# bontor_mbed_lowpan_rev_a.net
KiCad netlist of a schematic drawn in EAGLE
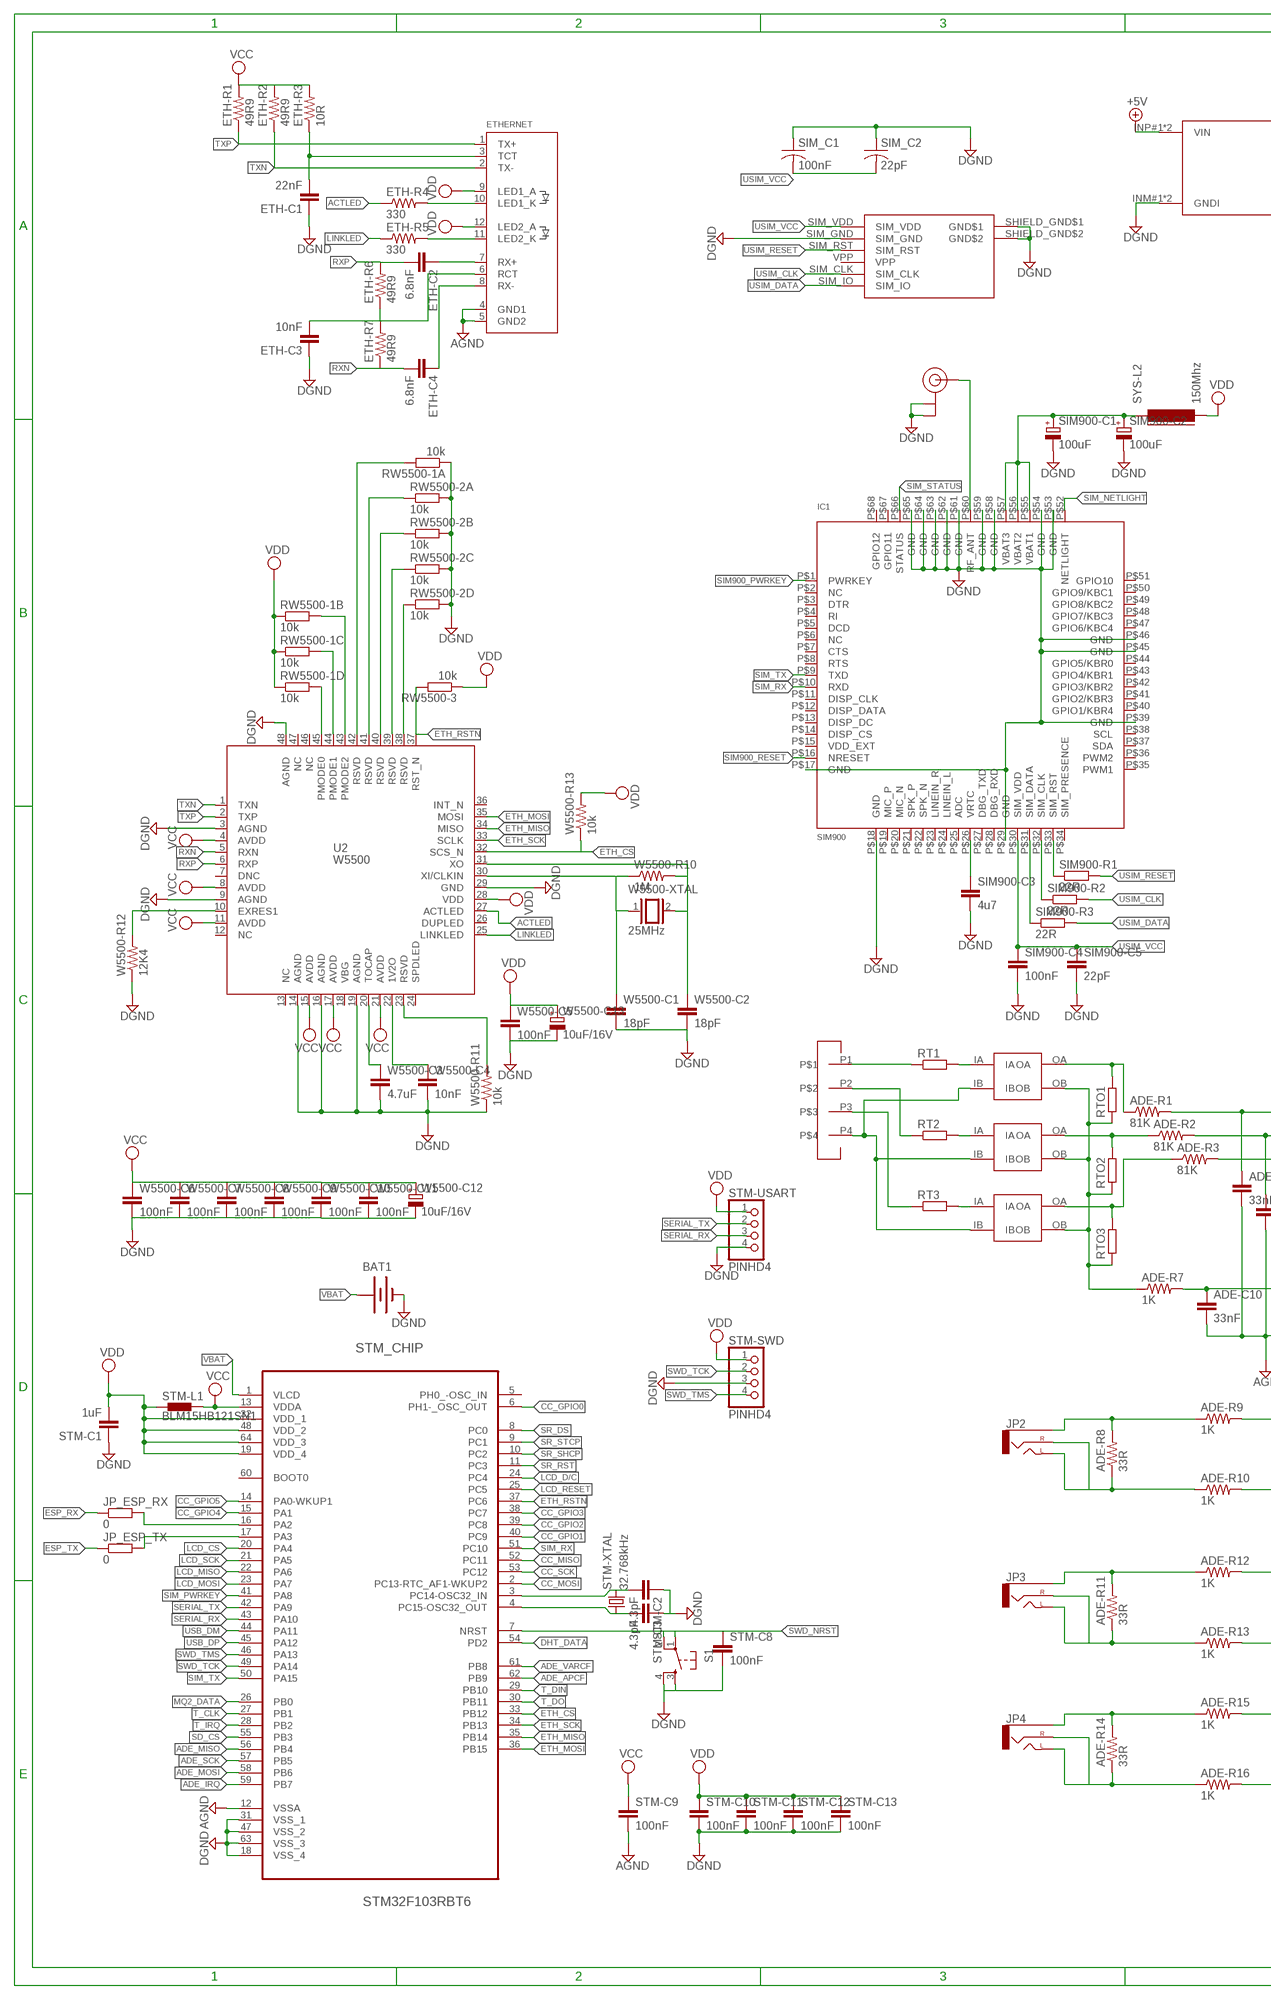
[diagram p0: schematic, sheet 1, part 1 of 2]
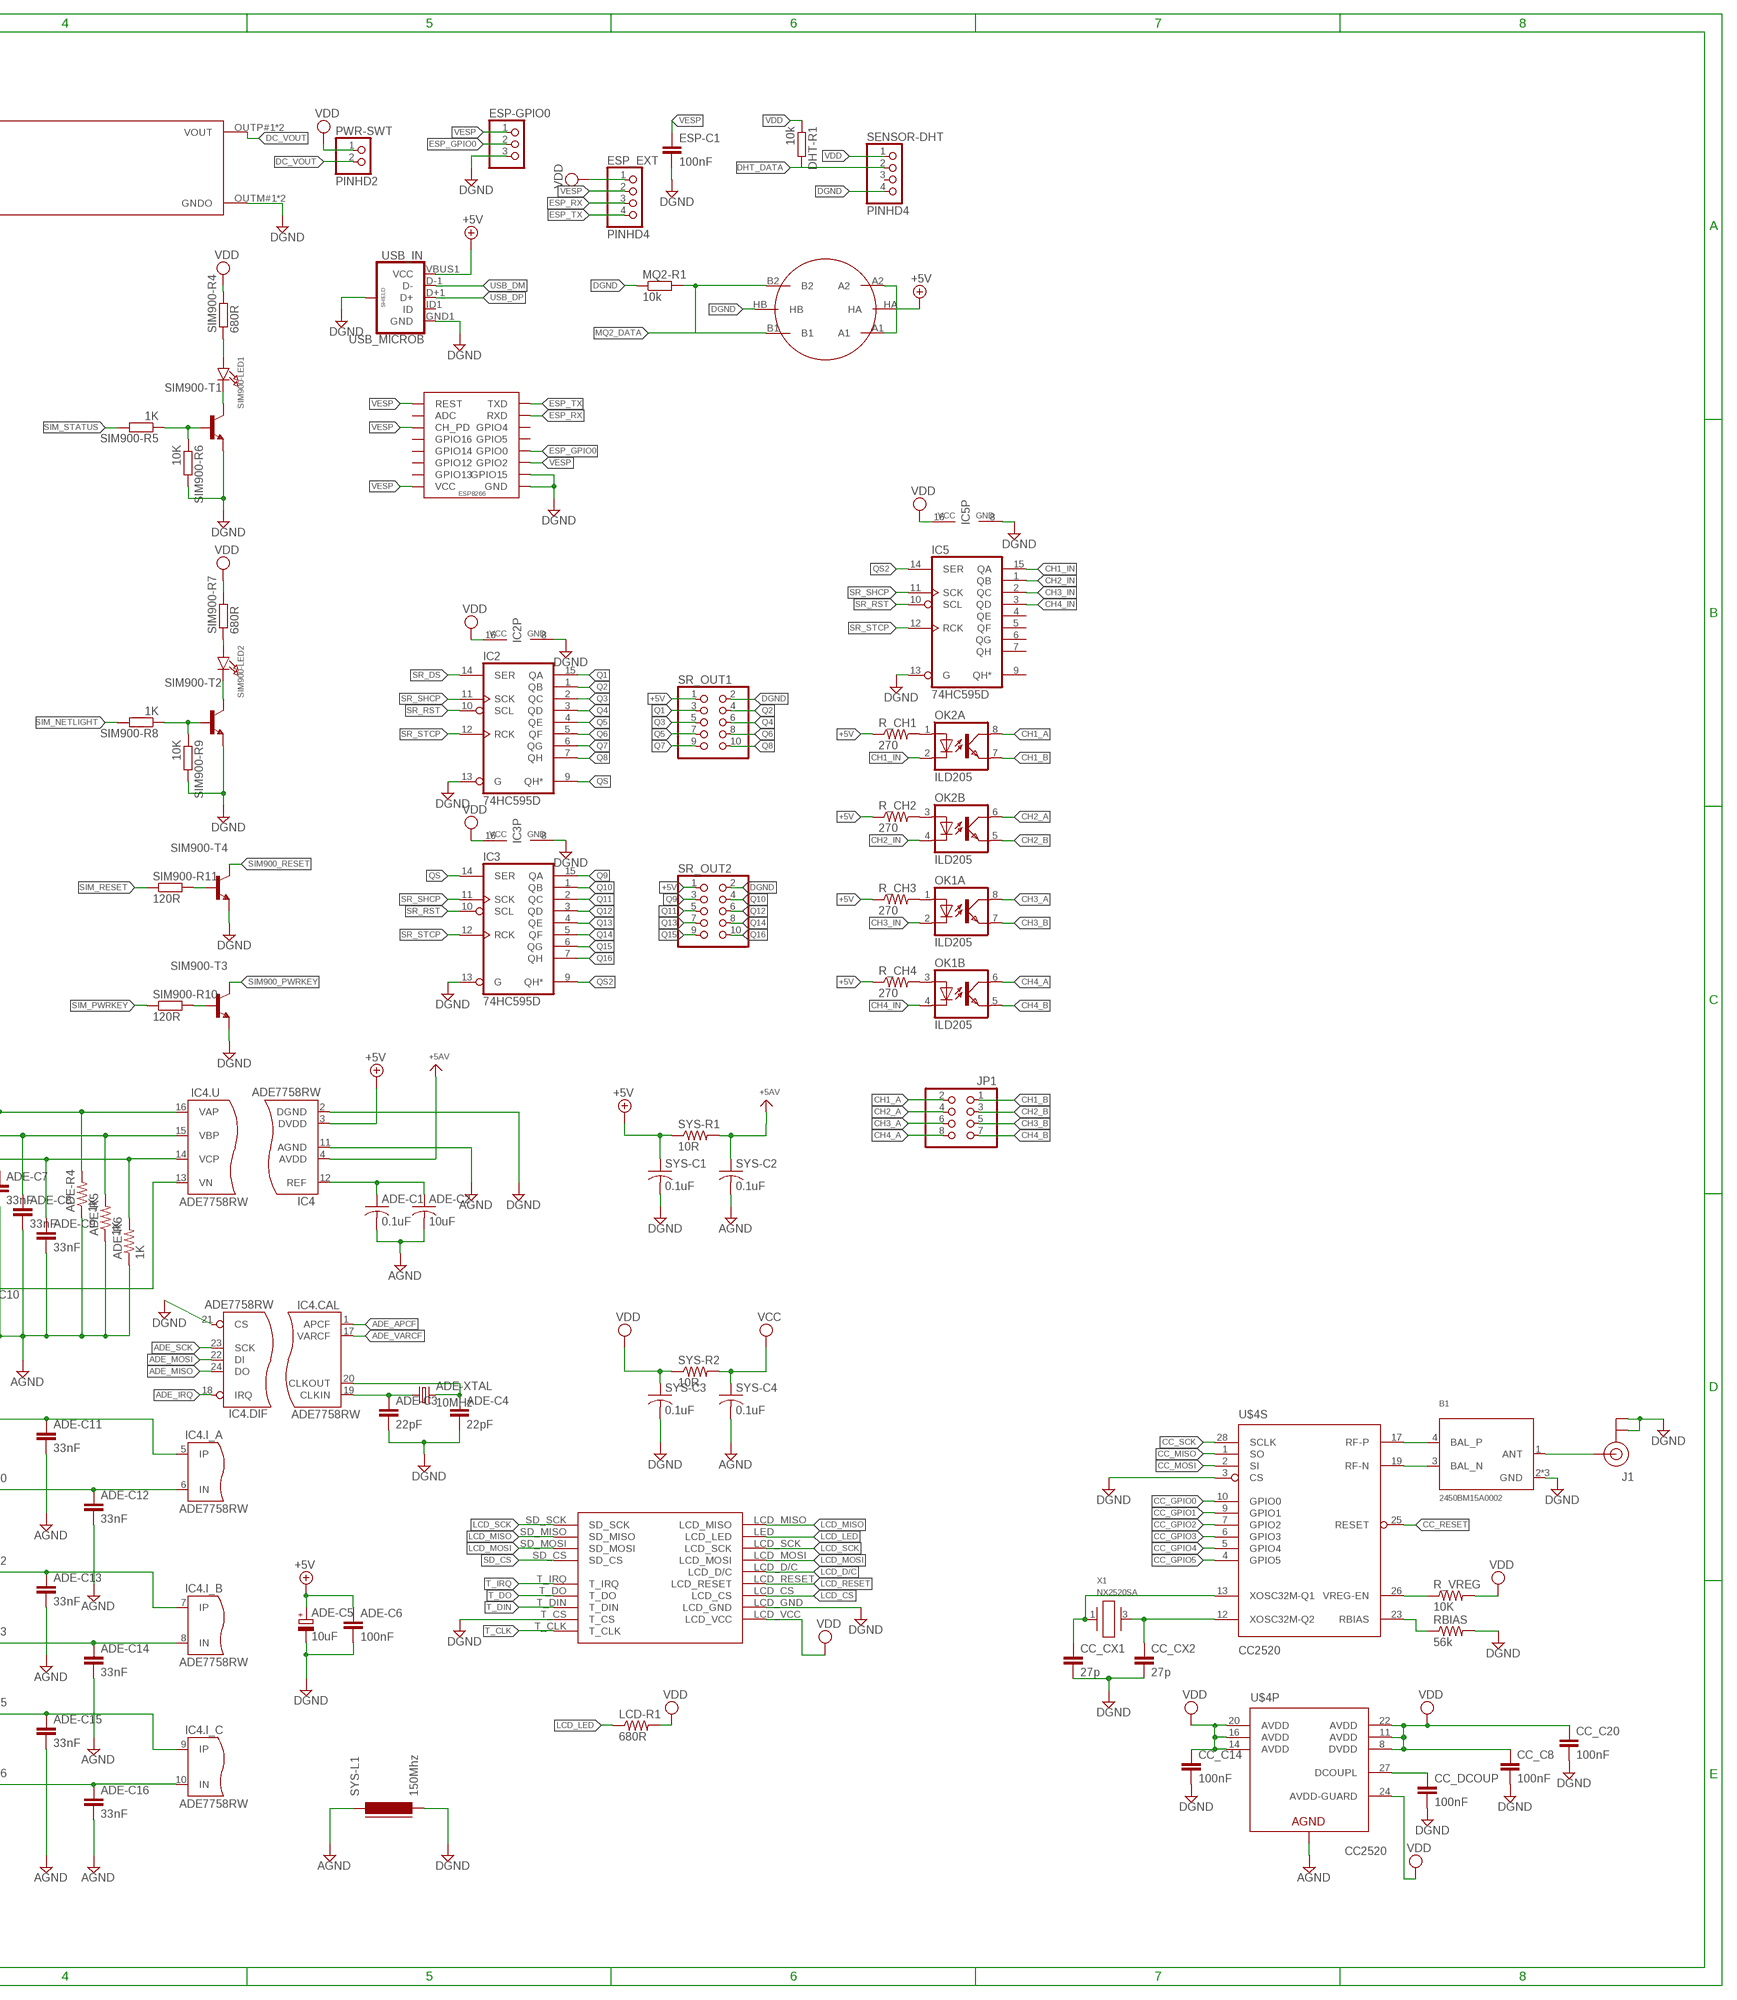
[diagram p1: schematic, sheet 1, part 2 of 2]

(export (version "E")
  (design (tool "Eeschema 10.0.6"))
  (components
    (comp (ref "ADE-C1")
      (value "0.1uF")
      (footprint "eagle-import:C0603@1")
      (libsource (lib "eagle-import") (part "C-USC0603"))
    )
    (comp (ref "ADE-C2")
      (value "10uF")
      (footprint "eagle-import:C0805K")
      (libsource (lib "eagle-import") (part "C-USC0805K"))
    )
    (comp (ref "ADE-C3")
      (value "22pF")
      (footprint "eagle-import:C0603")
      (libsource (lib "eagle-import") (part "C-EUC0603"))
    )
    (comp (ref "ADE-C4")
      (value "22pF")
      (footprint "eagle-import:C0603")
      (libsource (lib "eagle-import") (part "C-EUC0603"))
    )
    (comp (ref "ADE-C5")
      (value "10uF")
      (footprint "eagle-import:153CLV-0605")
      (libsource (lib "eagle-import") (part "CPOL-EU153CLV-0605"))
    )
    (comp (ref "ADE-C6")
      (value "100nF")
      (footprint "eagle-import:C0603")
      (libsource (lib "eagle-import") (part "C-EUC0603"))
    )
    (comp (ref "ADE-C7")
      (value "33nF")
      (footprint "eagle-import:0603-CAP")
      (libsource (lib "eagle-import") (part "CAP0603-CAP"))
    )
    (comp (ref "ADE-C8")
      (value "33nF")
      (footprint "eagle-import:0603-CAP")
      (libsource (lib "eagle-import") (part "CAP0603-CAP"))
    )
    (comp (ref "ADE-C9")
      (value "33nF")
      (footprint "eagle-import:0603-CAP")
      (libsource (lib "eagle-import") (part "CAP0603-CAP"))
    )
    (comp (ref "ADE-C10")
      (value "33nF")
      (footprint "eagle-import:0603-CAP")
      (libsource (lib "eagle-import") (part "CAP0603-CAP"))
    )
    (comp (ref "ADE-C11")
      (value "33nF")
      (footprint "eagle-import:0603-CAP")
      (libsource (lib "eagle-import") (part "CAP0603-CAP"))
    )
    (comp (ref "ADE-C12")
      (value "33nF")
      (footprint "eagle-import:0603-CAP")
      (libsource (lib "eagle-import") (part "CAP0603-CAP"))
    )
    (comp (ref "ADE-C13")
      (value "33nF")
      (footprint "eagle-import:0603-CAP")
      (libsource (lib "eagle-import") (part "CAP0603-CAP"))
    )
    (comp (ref "ADE-C14")
      (value "33nF")
      (footprint "eagle-import:0603-CAP")
      (libsource (lib "eagle-import") (part "CAP0603-CAP"))
    )
    (comp (ref "ADE-C15")
      (value "33nF")
      (footprint "eagle-import:0603-CAP")
      (libsource (lib "eagle-import") (part "CAP0603-CAP"))
    )
    (comp (ref "ADE-C16")
      (value "33nF")
      (footprint "eagle-import:0603-CAP")
      (libsource (lib "eagle-import") (part "CAP0603-CAP"))
    )
    (comp (ref "ADE-R1")
      (value "81K")
      (footprint "eagle-import:0603-RES")
      (libsource (lib "eagle-import") (part "RESISTOR0603-RES"))
    )
    (comp (ref "ADE-R2")
      (value "81K")
      (footprint "eagle-import:0603-RES")
      (libsource (lib "eagle-import") (part "RESISTOR0603-RES"))
    )
    (comp (ref "ADE-R3")
      (value "81K")
      (footprint "eagle-import:0603-RES")
      (libsource (lib "eagle-import") (part "RESISTOR0603-RES"))
    )
    (comp (ref "ADE-R4")
      (value "1K")
      (footprint "eagle-import:0603-RES")
      (libsource (lib "eagle-import") (part "RESISTOR0603-RES"))
    )
    (comp (ref "ADE-R5")
      (value "1K")
      (footprint "eagle-import:0603-RES")
      (libsource (lib "eagle-import") (part "RESISTOR0603-RES"))
    )
    (comp (ref "ADE-R6")
      (value "1K")
      (footprint "eagle-import:0603-RES")
      (libsource (lib "eagle-import") (part "RESISTOR0603-RES"))
    )
    (comp (ref "ADE-R7")
      (value "1K")
      (footprint "eagle-import:0603-RES")
      (libsource (lib "eagle-import") (part "RESISTOR0603-RES"))
    )
    (comp (ref "ADE-R8")
      (value "33R")
      (footprint "eagle-import:0603-RES")
      (libsource (lib "eagle-import") (part "RESISTOR0603-RES"))
    )
    (comp (ref "ADE-R9")
      (value "1K")
      (footprint "eagle-import:0603-RES")
      (libsource (lib "eagle-import") (part "RESISTOR0603-RES"))
    )
    (comp (ref "ADE-R10")
      (value "1K")
      (footprint "eagle-import:0603-RES")
      (libsource (lib "eagle-import") (part "RESISTOR0603-RES"))
    )
    (comp (ref "ADE-R11")
      (value "33R")
      (footprint "eagle-import:0603-RES")
      (libsource (lib "eagle-import") (part "RESISTOR0603-RES"))
    )
    (comp (ref "ADE-R12")
      (value "1K")
      (footprint "eagle-import:0603-RES")
      (libsource (lib "eagle-import") (part "RESISTOR0603-RES"))
    )
    (comp (ref "ADE-R13")
      (value "1K")
      (footprint "eagle-import:0603-RES")
      (libsource (lib "eagle-import") (part "RESISTOR0603-RES"))
    )
    (comp (ref "ADE-R14")
      (value "33R")
      (footprint "eagle-import:0603-RES")
      (libsource (lib "eagle-import") (part "RESISTOR0603-RES"))
    )
    (comp (ref "ADE-R15")
      (value "1K")
      (footprint "eagle-import:0603-RES")
      (libsource (lib "eagle-import") (part "RESISTOR0603-RES"))
    )
    (comp (ref "ADE-R16")
      (value "1K")
      (footprint "eagle-import:0603-RES")
      (libsource (lib "eagle-import") (part "RESISTOR0603-RES"))
    )
    (comp (ref "ADE-XTAL")
      (value "10MHz")
      (footprint "eagle-import:HC49US")
      (libsource (lib "eagle-import") (part "CRYSTALHC49US"))
    )
    (comp (ref "B1")
      (value "2450BM15A0002")
      (footprint "eagle-import:2450BM")
      (libsource (lib "eagle-import") (part "2450BM15A0002"))
    )
    (comp (ref "BAT1")
      (value "BATTERY12MM")
      (footprint "eagle-import:BATTCON_12MM")
      (libsource (lib "eagle-import") (part "BATTERY12MM"))
    )
    (comp (ref "CC_C8")
      (value "100nF")
      (footprint "eagle-import:C0402")
      (libsource (lib "eagle-import") (part "C-EUC0402"))
    )
    (comp (ref "CC_C14")
      (value "100nF")
      (footprint "eagle-import:C0402")
      (libsource (lib "eagle-import") (part "C-EUC0402"))
    )
    (comp (ref "CC_C20")
      (value "100nF")
      (footprint "eagle-import:C0402")
      (libsource (lib "eagle-import") (part "C-EUC0402"))
    )
    (comp (ref "CC_CX1")
      (value "27p")
      (footprint "eagle-import:C0201")
      (libsource (lib "eagle-import") (part "C-EUC0201"))
    )
    (comp (ref "CC_CX2")
      (value "27p")
      (footprint "eagle-import:C0201")
      (libsource (lib "eagle-import") (part "C-EUC0201"))
    )
    (comp (ref "CC_DCOUP")
      (value "100nF")
      (footprint "eagle-import:C0402")
      (libsource (lib "eagle-import") (part "C-EUC0402"))
    )
    (comp (ref "DCDC-3.5V")
      (value "DCDCMODULE_SMALL")
      (footprint "eagle-import:DCDCMODULE-SMALL")
      (libsource (lib "eagle-import") (part "DCDCMODULE_SMALL"))
    )
    (comp (ref "DHT-R1")
      (value "10k")
      (footprint "eagle-import:R0603")
      (libsource (lib "eagle-import") (part "resistor_R-EU_R0603"))
    )
    (comp (ref "ESP-C1")
      (value "100nF")
      (footprint "eagle-import:C0603")
      (libsource (lib "eagle-import") (part "C-EUC0603"))
    )
    (comp (ref "ESP-GPIO0")
      (value "PINHD-1X3")
      (footprint "eagle-import:1X03")
      (libsource (lib "eagle-import") (part "PINHD-1X3"))
    )
    (comp (ref "ESP_EXT")
      (value "PINHD4")
      (footprint "eagle-import:PINHD4")
      (libsource (lib "eagle-import") (part "PINHD4"))
    )
    (comp (ref "ETH-C1")
      (value "22nF")
      (footprint "eagle-import:C0603")
      (libsource (lib "eagle-import") (part "C-EUC0603"))
    )
    (comp (ref "ETH-C2")
      (value "6.8nF")
      (footprint "eagle-import:C0603")
      (libsource (lib "eagle-import") (part "C-EUC0603"))
    )
    (comp (ref "ETH-C3")
      (value "10nF")
      (footprint "eagle-import:C0603")
      (libsource (lib "eagle-import") (part "C-EUC0603"))
    )
    (comp (ref "ETH-C4")
      (value "6.8nF")
      (footprint "eagle-import:C0603")
      (libsource (lib "eagle-import") (part "C-EUC0603"))
    )
    (comp (ref "ETH-R1")
      (value "49R9")
      (footprint "eagle-import:R0603")
      (libsource (lib "eagle-import") (part "R-US_R0603"))
    )
    (comp (ref "ETH-R2")
      (value "49R9")
      (footprint "eagle-import:R0603")
      (libsource (lib "eagle-import") (part "R-US_R0603"))
    )
    (comp (ref "ETH-R3")
      (value "10R")
      (footprint "eagle-import:R0603")
      (libsource (lib "eagle-import") (part "R-US_R0603"))
    )
    (comp (ref "ETH-R4")
      (value "330")
      (footprint "eagle-import:R0603")
      (libsource (lib "eagle-import") (part "R-US_R0603"))
    )
    (comp (ref "ETH-R5")
      (value "330")
      (footprint "eagle-import:R0603")
      (libsource (lib "eagle-import") (part "R-US_R0603"))
    )
    (comp (ref "ETH-R6")
      (value "49R9")
      (footprint "eagle-import:R0603")
      (libsource (lib "eagle-import") (part "R-US_R0603"))
    )
    (comp (ref "ETH-R7")
      (value "49R9")
      (footprint "eagle-import:R0603")
      (libsource (lib "eagle-import") (part "R-US_R0603"))
    )
    (comp (ref "ETHERNET")
      (value "RJ45J0026D21BNL")
      (footprint "eagle-import:RJ45_PULSEJACK")
      (libsource (lib "eagle-import") (part "RJ45J0026D21BNL"))
    )
    (comp (ref "IC1")
      (value "SIM900")
      (footprint "eagle-import:SIM900_SMT")
      (libsource (lib "eagle-import") (part "GSM_SIM900_LITERAL"))
    )
    (comp (ref "IC2")
      (value "74HC595D")
      (footprint "eagle-import:SO16")
      (libsource (lib "eagle-import") (part "74595DHC"))
    )
    (comp (ref "IC3")
      (value "74HC595D")
      (footprint "eagle-import:SO16")
      (libsource (lib "eagle-import") (part "74595DHC"))
    )
    (comp (ref "IC4")
      (value "ADE7758RW")
      (footprint "eagle-import:SOIC24")
      (libsource (lib "eagle-import") (part "ADE7758RW"))
    )
    (comp (ref "IC5")
      (value "74HC595D")
      (footprint "eagle-import:SO16")
      (libsource (lib "eagle-import") (part "74595DHC"))
    )
    (comp (ref "J1")
      (value "U.FL")
      (footprint "eagle-import:U.FL")
      (libsource (lib "eagle-import") (part "SparkFun-Connectors_U.FL"))
    )
    (comp (ref "JP1")
      (value "PINHD-2X4")
      (footprint "eagle-import:2X04")
      (libsource (lib "eagle-import") (part "PINHD-2X4"))
    )
    (comp (ref "JP2")
      (value "AUDIO-JACKSMD2")
      (footprint "eagle-import:AUDIO-JACK-3.5MM-SMD")
      (libsource (lib "eagle-import") (part "AUDIO-JACKSMD2"))
    )
    (comp (ref "JP3")
      (value "AUDIO-JACKSMD2")
      (footprint "eagle-import:AUDIO-JACK-3.5MM-SMD")
      (libsource (lib "eagle-import") (part "AUDIO-JACKSMD2"))
    )
    (comp (ref "JP4")
      (value "AUDIO-JACKSMD2")
      (footprint "eagle-import:AUDIO-JACK-3.5MM-SMD")
      (libsource (lib "eagle-import") (part "AUDIO-JACKSMD2"))
    )
    (comp (ref "JP_ESP_RX")
      (value "0")
      (footprint "eagle-import:R0201")
      (libsource (lib "eagle-import") (part "R-EU_R0201"))
    )
    (comp (ref "JP_ESP_TX")
      (value "0")
      (footprint "eagle-import:R0201")
      (libsource (lib "eagle-import") (part "R-EU_R0201"))
    )
    (comp (ref "LCD-R1")
      (value "680R")
      (footprint "eagle-import:0603-RES")
      (libsource (lib "eagle-import") (part "RESISTOR0603-RES"))
    )
    (comp (ref "MQ2-R1")
      (value "10k")
      (footprint "eagle-import:R0603")
      (libsource (lib "eagle-import") (part "resistor_R-EU_R0603"))
    )
    (comp (ref "OK1")
      (value "ILD205")
      (footprint "eagle-import:SOIC08")
      (fields (field (name "MF") "VISHAY/TELEFUNKEN") (field (name "MPN") "ILD205T"))
      (libsource (lib "eagle-import") (part "ILD205"))
    )
    (comp (ref "OK2")
      (value "ILD205")
      (footprint "eagle-import:SOIC08")
      (fields (field (name "MF") "VISHAY/TELEFUNKEN") (field (name "MPN") "ILD205T"))
      (libsource (lib "eagle-import") (part "ILD205"))
    )
    (comp (ref "PWR-SWT")
      (value "PINHD2")
      (footprint "eagle-import:PINHD2")
      (libsource (lib "eagle-import") (part "PINHD2"))
    )
    (comp (ref "RBIAS")
      (value "56k")
      (footprint "eagle-import:0402-RES")
      (libsource (lib "eagle-import") (part "RESISTOR0402-RES"))
    )
    (comp (ref "RT1")
      (value "R-EU_0309/V")
      (footprint "eagle-import:0309V")
      (libsource (lib "eagle-import") (part "R-EU_0309/V"))
    )
    (comp (ref "RT2")
      (value "R-EU_0309/V")
      (footprint "eagle-import:0309V")
      (libsource (lib "eagle-import") (part "R-EU_0309/V"))
    )
    (comp (ref "RT3")
      (value "R-EU_0309/V")
      (footprint "eagle-import:0309V")
      (libsource (lib "eagle-import") (part "R-EU_0309/V"))
    )
    (comp (ref "RTO1")
      (value "R-EU_0309/12")
      (footprint "eagle-import:0309_12")
      (libsource (lib "eagle-import") (part "R-EU_0309/12"))
    )
    (comp (ref "RTO2")
      (value "R-EU_0309/12")
      (footprint "eagle-import:0309_12")
      (libsource (lib "eagle-import") (part "R-EU_0309/12"))
    )
    (comp (ref "RTO3")
      (value "R-EU_0309/12")
      (footprint "eagle-import:0309_12")
      (libsource (lib "eagle-import") (part "R-EU_0309/12"))
    )
    (comp (ref "RW5500-1")
      (value "10k")
      (footprint "eagle-import:RN8P-4R-CRA06S")
      (libsource (lib "eagle-import") (part "RESISTOR_ARRAY_4"))
    )
    (comp (ref "RW5500-2")
      (value "10k")
      (footprint "eagle-import:RN8P-4R-CRA06S")
      (libsource (lib "eagle-import") (part "RESISTOR_ARRAY_4"))
    )
    (comp (ref "RW5500-3")
      (value "10k")
      (footprint "eagle-import:R0603")
      (libsource (lib "eagle-import") (part "R-EU_R0603"))
    )
    (comp (ref "R_CH1")
      (value "270")
      (footprint "eagle-import:0603-RES")
      (libsource (lib "eagle-import") (part "RESISTOR0603-RES"))
    )
    (comp (ref "R_CH2")
      (value "270")
      (footprint "eagle-import:0603-RES")
      (libsource (lib "eagle-import") (part "RESISTOR0603-RES"))
    )
    (comp (ref "R_CH3")
      (value "270")
      (footprint "eagle-import:0603-RES")
      (libsource (lib "eagle-import") (part "RESISTOR0603-RES"))
    )
    (comp (ref "R_CH4")
      (value "270")
      (footprint "eagle-import:0603-RES")
      (libsource (lib "eagle-import") (part "RESISTOR0603-RES"))
    )
    (comp (ref "R_VREG")
      (value "10K")
      (footprint "eagle-import:0402-RES")
      (libsource (lib "eagle-import") (part "RESISTOR0402-RES"))
    )
    (comp (ref "S1")
      (value "TAC_SWITCHSMD")
      (footprint "eagle-import:TACTILE-SWITCH-SMD")
      (libsource (lib "eagle-import") (part "TAC_SWITCHSMD"))
    )
    (comp (ref "SENSOR-DHT")
      (value "PINHD4")
      (footprint "eagle-import:PINHD4")
      (libsource (lib "eagle-import") (part "PINHD4"))
    )
    (comp (ref "SENSOR-MQ2")
      (value "METHANE_SENSOR")
      (footprint "eagle-import:MQ-3")
      (libsource (lib "eagle-import") (part "METHANE_SENSOR"))
    )
    (comp (ref "SIM900-C1")
      (value "100uF")
      (footprint "eagle-import:153CLV-0605")
      (libsource (lib "eagle-import") (part "CPOL-EU153CLV-0605"))
    )
    (comp (ref "SIM900-C2")
      (value "100uF")
      (footprint "eagle-import:153CLV-0605")
      (libsource (lib "eagle-import") (part "CPOL-EU153CLV-0605"))
    )
    (comp (ref "SIM900-C3")
      (value "4u7")
      (footprint "eagle-import:C0603")
      (libsource (lib "eagle-import") (part "C-EUC0603"))
    )
    (comp (ref "SIM900-C4")
      (value "100nF")
      (footprint "eagle-import:C0603")
      (libsource (lib "eagle-import") (part "C-EUC0603"))
    )
    (comp (ref "SIM900-C5")
      (value "22pF")
      (footprint "eagle-import:C0603")
      (libsource (lib "eagle-import") (part "C-EUC0603"))
    )
    (comp (ref "SIM900-LED1")
      (value "LED0805_NOOUTLINE")
      (footprint "eagle-import:CHIPLED_0805_NOOUTLINE")
      (libsource (lib "eagle-import") (part "LED0805_NOOUTLINE"))
    )
    (comp (ref "SIM900-LED2")
      (value "LED0805_NOOUTLINE")
      (footprint "eagle-import:CHIPLED_0805_NOOUTLINE")
      (libsource (lib "eagle-import") (part "LED0805_NOOUTLINE"))
    )
    (comp (ref "SIM900-R1")
      (value "22R")
      (footprint "eagle-import:R0603")
      (libsource (lib "eagle-import") (part "R-EU_R0603"))
    )
    (comp (ref "SIM900-R2")
      (value "22R")
      (footprint "eagle-import:R0603")
      (libsource (lib "eagle-import") (part "R-EU_R0603"))
    )
    (comp (ref "SIM900-R3")
      (value "22R")
      (footprint "eagle-import:R0603")
      (libsource (lib "eagle-import") (part "R-EU_R0603"))
    )
    (comp (ref "SIM900-R4")
      (value "680R")
      (footprint "eagle-import:R0603")
      (libsource (lib "eagle-import") (part "R-EU_R0603"))
    )
    (comp (ref "SIM900-R5")
      (value "1K")
      (footprint "eagle-import:R0603")
      (libsource (lib "eagle-import") (part "R-EU_R0603"))
    )
    (comp (ref "SIM900-R6")
      (value "10K")
      (footprint "eagle-import:R0603")
      (libsource (lib "eagle-import") (part "R-EU_R0603"))
    )
    (comp (ref "SIM900-R7")
      (value "680R")
      (footprint "eagle-import:R0603")
      (libsource (lib "eagle-import") (part "R-EU_R0603"))
    )
    (comp (ref "SIM900-R8")
      (value "1K")
      (footprint "eagle-import:R0603")
      (libsource (lib "eagle-import") (part "R-EU_R0603"))
    )
    (comp (ref "SIM900-R9")
      (value "10K")
      (footprint "eagle-import:R0603")
      (libsource (lib "eagle-import") (part "R-EU_R0603"))
    )
    (comp (ref "SIM900-R10")
      (value "120R")
      (footprint "eagle-import:R0603")
      (libsource (lib "eagle-import") (part "resistor_R-EU_R0603"))
    )
    (comp (ref "SIM900-R11")
      (value "120R")
      (footprint "eagle-import:R0603")
      (libsource (lib "eagle-import") (part "resistor_R-EU_R0603"))
    )
    (comp (ref "SIM900-T1")
      (value "MMBT2222ALT1-NPN-SOT23-BEC")
      (footprint "eagle-import:SOT23-BEC")
      (libsource (lib "eagle-import") (part "-NPN-SOT23-BECMMBT2222ALT1"))
    )
    (comp (ref "SIM900-T2")
      (value "MMBT2222ALT1-NPN-SOT23-BEC")
      (footprint "eagle-import:SOT23-BEC")
      (libsource (lib "eagle-import") (part "-NPN-SOT23-BECMMBT2222ALT1"))
    )
    (comp (ref "SIM900-T3")
      (value "MMBT2222ALT1-NPN-SOT23-BEC")
      (footprint "eagle-import:SOT23-BEC")
      (libsource (lib "eagle-import") (part "transistor-neu-to92_-NPN-SOT23-BECMMBT2222ALT1"))
    )
    (comp (ref "SIM900-T4")
      (value "MMBT2222ALT1-NPN-SOT23-BEC")
      (footprint "eagle-import:SOT23-BEC")
      (libsource (lib "eagle-import") (part "transistor-neu-to92_-NPN-SOT23-BECMMBT2222ALT1"))
    )
    (comp (ref "SIM_C1")
      (value "100nF")
      (footprint "eagle-import:C0603K")
      (libsource (lib "eagle-import") (part "C-USC0603K"))
    )
    (comp (ref "SIM_C2")
      (value "22pF")
      (footprint "eagle-import:C0603K")
      (libsource (lib "eagle-import") (part "C-USC0603K"))
    )
    (comp (ref "SR_OUT1")
      (value "PINHD-2X5/90")
      (footprint "eagle-import:2X05_90")
      (libsource (lib "eagle-import") (part "PINHD-2X5/90"))
    )
    (comp (ref "SR_OUT2")
      (value "PINHD-2X5/90")
      (footprint "eagle-import:2X05_90")
      (libsource (lib "eagle-import") (part "PINHD-2X5/90"))
    )
    (comp (ref "STM-C1")
      (value "1uF")
      (footprint "eagle-import:C0603")
      (libsource (lib "eagle-import") (part "C-EUC0603"))
    )
    (comp (ref "STM-C2")
      (value "4.3pF")
      (footprint "eagle-import:C0603")
      (libsource (lib "eagle-import") (part "C-EUC0603"))
    )
    (comp (ref "STM-C3")
      (value "4.3pF")
      (footprint "eagle-import:C0603")
      (libsource (lib "eagle-import") (part "C-EUC0603"))
    )
    (comp (ref "STM-C8")
      (value "100nF")
      (footprint "eagle-import:C0603")
      (libsource (lib "eagle-import") (part "C-EUC0603"))
    )
    (comp (ref "STM-C9")
      (value "100nF")
      (footprint "eagle-import:C0603")
      (libsource (lib "eagle-import") (part "C-EUC0603"))
    )
    (comp (ref "STM-C10")
      (value "100nF")
      (footprint "eagle-import:C0603")
      (libsource (lib "eagle-import") (part "C-EUC0603"))
    )
    (comp (ref "STM-C11")
      (value "100nF")
      (footprint "eagle-import:C0603")
      (libsource (lib "eagle-import") (part "C-EUC0603"))
    )
    (comp (ref "STM-C12")
      (value "100nF")
      (footprint "eagle-import:C0603")
      (libsource (lib "eagle-import") (part "C-EUC0603"))
    )
    (comp (ref "STM-C13")
      (value "100nF")
      (footprint "eagle-import:C0603")
      (libsource (lib "eagle-import") (part "C-EUC0603"))
    )
    (comp (ref "STM-L1")
      (value "BLM15HB121SN1")
      (footprint "eagle-import:0402")
      (libsource (lib "eagle-import") (part "BLM15HB121SN1"))
    )
    (comp (ref "STM-SWD")
      (value "PINHD4")
      (footprint "eagle-import:PINHD4")
      (libsource (lib "eagle-import") (part "PINHD4"))
    )
    (comp (ref "STM-USART")
      (value "PINHD4")
      (footprint "eagle-import:PINHD4")
      (libsource (lib "eagle-import") (part "PINHD4"))
    )
    (comp (ref "STM-XTAL")
      (value "32.768kHz")
      (footprint "eagle-import:TC26H")
      (libsource (lib "eagle-import") (part "CRYSTALTC26H"))
    )
    (comp (ref "STM_CHIP")
      (value "STM32F103RBT6")
      (footprint "eagle-import:QFP50P1200X1200X160-64N")
      (fields (field (name "MPN") "STM32L152RBT6"))
      (libsource (lib "eagle-import") (part "STM32L152RBT6"))
    )
    (comp (ref "SYS-C1")
      (value "0.1uF")
      (footprint "eagle-import:C0603@1")
      (libsource (lib "eagle-import") (part "C-USC0603"))
    )
    (comp (ref "SYS-C2")
      (value "0.1uF")
      (footprint "eagle-import:C0603@1")
      (libsource (lib "eagle-import") (part "C-USC0603"))
    )
    (comp (ref "SYS-C3")
      (value "0.1uF")
      (footprint "eagle-import:C0603@1")
      (libsource (lib "eagle-import") (part "C-USC0603"))
    )
    (comp (ref "SYS-C4")
      (value "0.1uF")
      (footprint "eagle-import:C0603@1")
      (libsource (lib "eagle-import") (part "C-USC0603"))
    )
    (comp (ref "SYS-L1")
      (value "150Mhz")
      (footprint "eagle-import:FB805")
      (libsource (lib "eagle-import") (part "FERRITE-0805"))
    )
    (comp (ref "SYS-L2")
      (value "150Mhz")
      (footprint "eagle-import:FB805")
      (libsource (lib "eagle-import") (part "FERRITE-0805"))
    )
    (comp (ref "SYS-R1")
      (value "10R")
      (footprint "eagle-import:0603-RES")
      (libsource (lib "eagle-import") (part "RESISTOR0603-RES"))
    )
    (comp (ref "SYS-R2")
      (value "10R")
      (footprint "eagle-import:0603-RES")
      (libsource (lib "eagle-import") (part "RESISTOR0603-RES"))
    )
    (comp (ref "U$4")
      (value "CC2520")
      (footprint "eagle-import:QFN50P500X500X100-29N")
      (libsource (lib "eagle-import") (part "CC2520"))
    )
    (comp (ref "U$5")
      (value "ESP8266WI12")
      (footprint "eagle-import:WI12")
      (libsource (lib "eagle-import") (part "ESP8266WI12"))
    )
    (comp (ref "U$7")
      (value "U.FL")
      (footprint "eagle-import:U.FL")
      (libsource (lib "eagle-import") (part "U.FL"))
    )
    (comp (ref "U$8")
      (value "SIM_HOLDER")
      (footprint "eagle-import:SIMHOLDER-PUSHPUSH")
      (libsource (lib "eagle-import") (part "SIM_HOLDER"))
    )
    (comp (ref "U$9")
      (value "TRANSFORMER")
      (footprint "eagle-import:TV16")
      (libsource (lib "eagle-import") (part "TRANSFORMER"))
    )
    (comp (ref "U$10")
      (value "TRANSFORMER")
      (footprint "eagle-import:TV16")
      (libsource (lib "eagle-import") (part "TRANSFORMER"))
    )
    (comp (ref "U$11")
      (value "TRANSFORMER")
      (footprint "eagle-import:TV16")
      (libsource (lib "eagle-import") (part "TRANSFORMER"))
    )
    (comp (ref "U$12")
      (value "TERMINAL_BLOCK")
      (footprint "eagle-import:TERMINAL-RIGHT-ANGLE")
      (libsource (lib "eagle-import") (part "TERMINAL_BLOCK"))
    )
    (comp (ref "U$13")
      (value "LCD_2.4")
      (footprint "eagle-import:LCD_TOUCH_2-4")
      (libsource (lib "eagle-import") (part "LCD_2.4"))
    )
    (comp (ref "U2")
      (value "W5500")
      (footprint "eagle-import:W5500")
      (libsource (lib "eagle-import") (part "W5500"))
    )
    (comp (ref "USB_IN")
      (value "USB_MICROB")
      (footprint "eagle-import:USB-B-MICRO-SMD_V03")
      (libsource (lib "eagle-import") (part "USB_MICROB_PLUGCONN-11752"))
    )
    (comp (ref "W5500-C1")
      (value "18pF")
      (footprint "eagle-import:C0603")
      (libsource (lib "eagle-import") (part "C-EUC0603"))
    )
    (comp (ref "W5500-C2")
      (value "18pF")
      (footprint "eagle-import:C0603")
      (libsource (lib "eagle-import") (part "C-EUC0603"))
    )
    (comp (ref "W5500-C3")
      (value "4.7uF")
      (footprint "eagle-import:C0603")
      (libsource (lib "eagle-import") (part "C-EUC0603"))
    )
    (comp (ref "W5500-C4")
      (value "10nF")
      (footprint "eagle-import:C0603")
      (libsource (lib "eagle-import") (part "C-EUC0603"))
    )
    (comp (ref "W5500-C5")
      (value "100nF")
      (footprint "eagle-import:C0603")
      (libsource (lib "eagle-import") (part "C-EUC0603"))
    )
    (comp (ref "W5500-C6")
      (value "100nF")
      (footprint "eagle-import:C0603")
      (libsource (lib "eagle-import") (part "C-EUC0603"))
    )
    (comp (ref "W5500-C7")
      (value "100nF")
      (footprint "eagle-import:C0603")
      (libsource (lib "eagle-import") (part "C-EUC0603"))
    )
    (comp (ref "W5500-C8")
      (value "100nF")
      (footprint "eagle-import:C0603")
      (libsource (lib "eagle-import") (part "C-EUC0603"))
    )
    (comp (ref "W5500-C9")
      (value "100nF")
      (footprint "eagle-import:C0603")
      (libsource (lib "eagle-import") (part "C-EUC0603"))
    )
    (comp (ref "W5500-C10")
      (value "100nF")
      (footprint "eagle-import:C0603")
      (libsource (lib "eagle-import") (part "C-EUC0603"))
    )
    (comp (ref "W5500-C11")
      (value "100nF")
      (footprint "eagle-import:C0603")
      (libsource (lib "eagle-import") (part "C-EUC0603"))
    )
    (comp (ref "W5500-C12")
      (value "10uF/16V")
      (footprint "eagle-import:153CLV-0605")
      (libsource (lib "eagle-import") (part "CPOL-EU153CLV-0605"))
    )
    (comp (ref "W5500-C13")
      (value "10uF/16V")
      (footprint "eagle-import:153CLV-0605")
      (libsource (lib "eagle-import") (part "CPOL-EU153CLV-0605"))
    )
    (comp (ref "W5500-R10")
      (value "1M")
      (footprint "eagle-import:R0603")
      (libsource (lib "eagle-import") (part "R-US_R0603"))
    )
    (comp (ref "W5500-R11")
      (value "10k")
      (footprint "eagle-import:R0603")
      (libsource (lib "eagle-import") (part "R-US_R0603"))
    )
    (comp (ref "W5500-R12")
      (value "12K4")
      (footprint "eagle-import:R0805")
      (libsource (lib "eagle-import") (part "R-US_R0805"))
    )
    (comp (ref "W5500-R13")
      (value "10k")
      (footprint "eagle-import:R0603")
      (libsource (lib "eagle-import") (part "R-US_R0603"))
    )
    (comp (ref "W5500-XTAL")
      (value "25MHz")
      (footprint "eagle-import:QS")
      (libsource (lib "eagle-import") (part "XTAL/S"))
    )
    (comp (ref "X1")
      (value "NX2520SA")
      (footprint "eagle-import:NX2520SA")
      (libsource (lib "eagle-import") (part "NX2520SA"))
    )
  )
  (nets
    (net (code "1") (name "+5AV") (class "Default")
      (node (ref "IC4") (pin "4") (pinfunction "AVDD_4") (pintype "power_in"))
      (node (ref "SYS-C2") (pin "1") (pinfunction "1_1") (pintype "passive"))
      (node (ref "SYS-R1") (pin "2") (pinfunction "2_2") (pintype "passive"))
    )
    (net (code "2") (name "+5V") (class "Default")
      (node (ref "ADE-C5") (pin "+") (pinfunction "+_+") (pintype "passive"))
      (node (ref "ADE-C6") (pin "1") (pinfunction "1_1") (pintype "passive"))
      (node (ref "DCDC-3.5V") (pin "INP#1") (pinfunction "VIN_INP#1") (pintype "bidirectional"))
      (node (ref "DCDC-3.5V") (pin "INP#2") (pinfunction "VIN_INP#2") (pintype "bidirectional"))
      (node (ref "IC4") (pin "3") (pinfunction "DVDD_3") (pintype "power_in"))
      (node (ref "R_CH1") (pin "1") (pinfunction "1_1") (pintype "passive"))
      (node (ref "R_CH2") (pin "1") (pinfunction "1_1") (pintype "passive"))
      (node (ref "R_CH3") (pin "1") (pinfunction "1_1") (pintype "passive"))
      (node (ref "R_CH4") (pin "1") (pinfunction "1_1") (pintype "passive"))
      (node (ref "SENSOR-MQ2") (pin "A1") (pinfunction "A1_A1") (pintype "bidirectional"))
      (node (ref "SENSOR-MQ2") (pin "A2") (pinfunction "A2_A2") (pintype "bidirectional"))
      (node (ref "SENSOR-MQ2") (pin "HA") (pinfunction "HA_HA") (pintype "bidirectional"))
      (node (ref "SR_OUT1") (pin "1") (pinfunction "1_1") (pintype "passive"))
      (node (ref "SR_OUT2") (pin "1") (pinfunction "1_1") (pintype "passive"))
      (node (ref "SYS-C1") (pin "1") (pinfunction "1_1") (pintype "passive"))
      (node (ref "SYS-R1") (pin "1") (pinfunction "1_1") (pintype "passive"))
      (node (ref "USB_IN") (pin "VBUS1") (pinfunction "VCC_VBUS1") (pintype "bidirectional"))
    )
    (net (code "3") (name "/GPIO11") (class "Default")
      (node (ref "IC1") (pin "P$67") (pinfunction "GPIO11_P$67") (pintype "power_in"))
    )
    (net (code "4") (name "/GPIO12") (class "Default")
      (node (ref "IC1") (pin "P$68") (pinfunction "GPIO12_P$68") (pintype "power_in"))
    )
    (net (code "5") (name "ACTLED") (class "Default")
      (node (ref "ETH-R4") (pin "1") (pinfunction "1_1") (pintype "passive"))
      (node (ref "U2") (pin "27") (pinfunction "ACTLED_27") (pintype "passive"))
    )
    (net (code "6") (name "ADE_APCF") (class "Default")
      (node (ref "IC4") (pin "1") (pinfunction "APCF_1") (pintype "output"))
      (node (ref "STM_CHIP") (pin "62") (pinfunction "PB9_62") (pintype "bidirectional"))
    )
    (net (code "7") (name "ADE_IRQ") (class "Default")
      (node (ref "IC4") (pin "18") (pinfunction "IRQ_18") (pintype "output"))
      (node (ref "STM_CHIP") (pin "59") (pinfunction "PB7_59") (pintype "bidirectional"))
    )
    (net (code "8") (name "ADE_MISO") (class "Default")
      (node (ref "IC4") (pin "24") (pinfunction "DO_24") (pintype "output"))
      (node (ref "STM_CHIP") (pin "56") (pinfunction "PB4_56") (pintype "bidirectional"))
    )
    (net (code "9") (name "ADE_MOSI") (class "Default")
      (node (ref "IC4") (pin "22") (pinfunction "DI_22") (pintype "input"))
      (node (ref "STM_CHIP") (pin "58") (pinfunction "PB6_58") (pintype "bidirectional"))
    )
    (net (code "10") (name "ADE_SCK") (class "Default")
      (node (ref "IC4") (pin "23") (pinfunction "SCK_23") (pintype "input"))
      (node (ref "STM_CHIP") (pin "57") (pinfunction "PB5_57") (pintype "bidirectional"))
    )
    (net (code "11") (name "ADE_VARCF") (class "Default")
      (node (ref "IC4") (pin "17") (pinfunction "VARCF_17") (pintype "output"))
      (node (ref "STM_CHIP") (pin "61") (pinfunction "PB8_61") (pintype "bidirectional"))
    )
    (net (code "12") (name "AGND") (class "Default")
      (node (ref "ADE-C1") (pin "2") (pinfunction "2_2") (pintype "passive"))
      (node (ref "ADE-C10") (pin "2") (pinfunction "2_2") (pintype "passive"))
      (node (ref "ADE-C11") (pin "2") (pinfunction "2_2") (pintype "passive"))
      (node (ref "ADE-C12") (pin "2") (pinfunction "2_2") (pintype "passive"))
      (node (ref "ADE-C13") (pin "2") (pinfunction "2_2") (pintype "passive"))
      (node (ref "ADE-C14") (pin "2") (pinfunction "2_2") (pintype "passive"))
      (node (ref "ADE-C15") (pin "2") (pinfunction "2_2") (pintype "passive"))
      (node (ref "ADE-C16") (pin "2") (pinfunction "2_2") (pintype "passive"))
      (node (ref "ADE-C2") (pin "2") (pinfunction "2_2") (pintype "passive"))
      (node (ref "ADE-C7") (pin "2") (pinfunction "2_2") (pintype "passive"))
      (node (ref "ADE-C8") (pin "2") (pinfunction "2_2") (pintype "passive"))
      (node (ref "ADE-C9") (pin "2") (pinfunction "2_2") (pintype "passive"))
      (node (ref "ADE-R4") (pin "1") (pinfunction "1_1") (pintype "passive"))
      (node (ref "ADE-R5") (pin "1") (pinfunction "1_1") (pintype "passive"))
      (node (ref "ADE-R6") (pin "1") (pinfunction "1_1") (pintype "passive"))
      (node (ref "ETHERNET") (pin "4") (pinfunction "GND1_4") (pintype "bidirectional"))
      (node (ref "ETHERNET") (pin "5") (pinfunction "GND2_5") (pintype "bidirectional"))
      (node (ref "IC4") (pin "11") (pinfunction "AGND_11") (pintype "power_in"))
      (node (ref "STM-C9") (pin "2") (pinfunction "2_2") (pintype "passive"))
      (node (ref "STM_CHIP") (pin "12") (pinfunction "VSSA_12") (pintype "power_in"))
      (node (ref "SYS-C2") (pin "2") (pinfunction "2_2") (pintype "passive"))
      (node (ref "SYS-C4") (pin "2") (pinfunction "2_2") (pintype "passive"))
      (node (ref "SYS-L1") (pin "1") (pinfunction "1_1") (pintype "passive"))
      (node (ref "U$4") (pin "29") (pinfunction "AGND_29") (pintype "power_in"))
    )
    (net (code "13") (name "CC_GPIO0") (class "Default")
      (node (ref "STM_CHIP") (pin "6") (pinfunction "PH1-_OSC_OUT_6") (pintype "bidirectional"))
      (node (ref "U$4") (pin "10") (pinfunction "GPIO0_10") (pintype "output"))
    )
    (net (code "14") (name "CC_GPIO1") (class "Default")
      (node (ref "STM_CHIP") (pin "40") (pinfunction "PC9_40") (pintype "bidirectional"))
      (node (ref "U$4") (pin "9") (pinfunction "GPIO1_9") (pintype "output"))
    )
    (net (code "15") (name "CC_GPIO2") (class "Default")
      (node (ref "STM_CHIP") (pin "39") (pinfunction "PC8_39") (pintype "bidirectional"))
      (node (ref "U$4") (pin "7") (pinfunction "GPIO2_7") (pintype "bidirectional"))
    )
    (net (code "16") (name "CC_GPIO3") (class "Default")
      (node (ref "STM_CHIP") (pin "38") (pinfunction "PC7_38") (pintype "bidirectional"))
      (node (ref "U$4") (pin "6") (pinfunction "GPIO3_6") (pintype "bidirectional"))
    )
    (net (code "17") (name "CC_GPIO4") (class "Default")
      (node (ref "STM_CHIP") (pin "15") (pinfunction "PA1_15") (pintype "bidirectional"))
      (node (ref "U$4") (pin "5") (pinfunction "GPIO4_5") (pintype "bidirectional"))
    )
    (net (code "18") (name "CC_GPIO5") (class "Default")
      (node (ref "STM_CHIP") (pin "14") (pinfunction "PA0-WKUP1_14") (pintype "bidirectional"))
      (node (ref "U$4") (pin "4") (pinfunction "GPIO5_4") (pintype "bidirectional"))
    )
    (net (code "19") (name "CC_MISO") (class "Default")
      (node (ref "STM_CHIP") (pin "52") (pinfunction "PC11_52") (pintype "bidirectional"))
      (node (ref "U$4") (pin "1") (pinfunction "SO_1") (pintype "output"))
    )
    (net (code "20") (name "CC_MOSI") (class "Default")
      (node (ref "STM_CHIP") (pin "2") (pinfunction "PC13-RTC_AF1-WKUP2_2") (pintype "bidirectional"))
      (node (ref "U$4") (pin "2") (pinfunction "SI_2") (pintype "input"))
    )
    (net (code "21") (name "CC_RESET") (class "Default")
      (node (ref "U$4") (pin "25") (pinfunction "RESET_25") (pintype "input"))
    )
    (net (code "22") (name "CC_SCK") (class "Default")
      (node (ref "STM_CHIP") (pin "53") (pinfunction "PC12_53") (pintype "bidirectional"))
      (node (ref "U$4") (pin "28") (pinfunction "SCLK_28") (pintype "input"))
    )
    (net (code "23") (name "CH1_A") (class "Default")
      (node (ref "JP1") (pin "2") (pinfunction "2_2") (pintype "passive"))
      (node (ref "OK2") (pin "8") (pinfunction "COL_8") (pintype "passive"))
    )
    (net (code "24") (name "CH1_B") (class "Default")
      (node (ref "JP1") (pin "1") (pinfunction "1_1") (pintype "passive"))
      (node (ref "OK2") (pin "7") (pinfunction "EMIT_7") (pintype "passive"))
    )
    (net (code "25") (name "CH1_IN") (class "Default")
      (node (ref "IC5") (pin "15") (pinfunction "QA_15") (pintype "tri_state"))
      (node (ref "OK2") (pin "2") (pinfunction "C_2") (pintype "passive"))
    )
    (net (code "26") (name "CH2_A") (class "Default")
      (node (ref "JP1") (pin "4") (pinfunction "4_4") (pintype "passive"))
      (node (ref "OK2") (pin "6") (pinfunction "COL_6") (pintype "passive"))
    )
    (net (code "27") (name "CH2_B") (class "Default")
      (node (ref "JP1") (pin "3") (pinfunction "3_3") (pintype "passive"))
      (node (ref "OK2") (pin "5") (pinfunction "EMIT_5") (pintype "passive"))
    )
    (net (code "28") (name "CH2_IN") (class "Default")
      (node (ref "IC5") (pin "1") (pinfunction "QB_1") (pintype "tri_state"))
      (node (ref "OK2") (pin "4") (pinfunction "C_4") (pintype "passive"))
    )
    (net (code "29") (name "CH3_A") (class "Default")
      (node (ref "JP1") (pin "6") (pinfunction "6_6") (pintype "passive"))
      (node (ref "OK1") (pin "8") (pinfunction "COL_8") (pintype "passive"))
    )
    (net (code "30") (name "CH3_B") (class "Default")
      (node (ref "JP1") (pin "5") (pinfunction "5_5") (pintype "passive"))
      (node (ref "OK1") (pin "7") (pinfunction "EMIT_7") (pintype "passive"))
    )
    (net (code "31") (name "CH3_IN") (class "Default")
      (node (ref "IC5") (pin "2") (pinfunction "QC_2") (pintype "tri_state"))
      (node (ref "OK1") (pin "2") (pinfunction "C_2") (pintype "passive"))
    )
    (net (code "32") (name "CH4_A") (class "Default")
      (node (ref "JP1") (pin "8") (pinfunction "8_8") (pintype "passive"))
      (node (ref "OK1") (pin "6") (pinfunction "COL_6") (pintype "passive"))
    )
    (net (code "33") (name "CH4_B") (class "Default")
      (node (ref "JP1") (pin "7") (pinfunction "7_7") (pintype "passive"))
      (node (ref "OK1") (pin "5") (pinfunction "EMIT_5") (pintype "passive"))
    )
    (net (code "34") (name "CH4_IN") (class "Default")
      (node (ref "IC5") (pin "3") (pinfunction "QD_3") (pintype "tri_state"))
      (node (ref "OK1") (pin "4") (pinfunction "C_4") (pintype "passive"))
    )
    (net (code "35") (name "DC_VOUT") (class "Default")
      (node (ref "DCDC-3.5V") (pin "OUTP#1") (pinfunction "VOUT_OUTP#1") (pintype "bidirectional"))
      (node (ref "DCDC-3.5V") (pin "OUTP#2") (pinfunction "VOUT_OUTP#2") (pintype "bidirectional"))
      (node (ref "PWR-SWT") (pin "2") (pinfunction "2_2") (pintype "passive"))
    )
    (net (code "36") (name "DGND") (class "Default")
      (node (ref "ADE-C3") (pin "2") (pinfunction "2_2") (pintype "passive"))
      (node (ref "ADE-C4") (pin "2") (pinfunction "2_2") (pintype "passive"))
      (node (ref "ADE-C5") (pin "-") (pinfunction "-_-") (pintype "passive"))
      (node (ref "ADE-C6") (pin "2") (pinfunction "2_2") (pintype "passive"))
      (node (ref "B1") (pin "2") (pinfunction "GND_2") (pintype "bidirectional"))
      (node (ref "B1") (pin "5") (pinfunction "GND_5") (pintype "bidirectional"))
      (node (ref "B1") (pin "6") (pinfunction "GND_6") (pintype "bidirectional"))
      (node (ref "BAT1") (pin "GND") (pinfunction "-_GND") (pintype "power_in"))
      (node (ref "CC_C14") (pin "2") (pinfunction "2_2") (pintype "passive"))
      (node (ref "CC_C20") (pin "2") (pinfunction "2_2") (pintype "passive"))
      (node (ref "CC_C8") (pin "2") (pinfunction "2_2") (pintype "passive"))
      (node (ref "CC_CX1") (pin "2") (pinfunction "2_2") (pintype "passive"))
      (node (ref "CC_CX2") (pin "2") (pinfunction "2_2") (pintype "passive"))
      (node (ref "CC_DCOUP") (pin "2") (pinfunction "2_2") (pintype "passive"))
      (node (ref "DCDC-3.5V") (pin "INM#1") (pinfunction "GNDI_INM#1") (pintype "bidirectional"))
      (node (ref "DCDC-3.5V") (pin "INM#2") (pinfunction "GNDI_INM#2") (pintype "bidirectional"))
      (node (ref "DCDC-3.5V") (pin "OUTM#1") (pinfunction "GNDO_OUTM#1") (pintype "bidirectional"))
      (node (ref "DCDC-3.5V") (pin "OUTM#2") (pinfunction "GNDO_OUTM#2") (pintype "bidirectional"))
      (node (ref "ESP-C1") (pin "2") (pinfunction "2_2") (pintype "passive"))
      (node (ref "ESP-GPIO0") (pin "3") (pinfunction "3_3") (pintype "passive"))
      (node (ref "ETH-C1") (pin "1") (pinfunction "1_1") (pintype "passive"))
      (node (ref "ETH-C3") (pin "1") (pinfunction "1_1") (pintype "passive"))
      (node (ref "IC1") (pin "P$17") (pinfunction "GND_P$17") (pintype "power_in"))
      (node (ref "IC1") (pin "P$18") (pinfunction "GND_P$18") (pintype "power_in"))
      (node (ref "IC1") (pin "P$29") (pinfunction "GND_P$29") (pintype "power_in"))
      (node (ref "IC1") (pin "P$39") (pinfunction "GND_P$39") (pintype "power_in"))
      (node (ref "IC1") (pin "P$45") (pinfunction "GND_P$45") (pintype "power_in"))
      (node (ref "IC1") (pin "P$46") (pinfunction "GND_P$46") (pintype "power_in"))
      (node (ref "IC1") (pin "P$53") (pinfunction "GND_P$53") (pintype "power_in"))
      (node (ref "IC1") (pin "P$54") (pinfunction "GND_P$54") (pintype "power_in"))
      (node (ref "IC1") (pin "P$58") (pinfunction "GND_P$58") (pintype "power_in"))
      (node (ref "IC1") (pin "P$59") (pinfunction "GND_P$59") (pintype "power_in"))
      (node (ref "IC1") (pin "P$61") (pinfunction "GND_P$61") (pintype "power_in"))
      (node (ref "IC1") (pin "P$62") (pinfunction "GND_P$62") (pintype "power_in"))
      (node (ref "IC1") (pin "P$63") (pinfunction "GND_P$63") (pintype "power_in"))
      (node (ref "IC1") (pin "P$64") (pinfunction "GND_P$64") (pintype "power_in"))
      (node (ref "IC1") (pin "P$65") (pinfunction "GND_P$65") (pintype "power_in"))
      (node (ref "IC2") (pin "13") (pinfunction "G_13") (pintype "input"))
      (node (ref "IC2") (pin "8") (pinfunction "GND_8") (pintype "power_in"))
      (node (ref "IC3") (pin "13") (pinfunction "G_13") (pintype "input"))
      (node (ref "IC3") (pin "8") (pinfunction "GND_8") (pintype "power_in"))
      (node (ref "IC4") (pin "2") (pinfunction "DGND_2") (pintype "power_in"))
      (node (ref "IC4") (pin "21") (pinfunction "CS_21") (pintype "input"))
      (node (ref "IC5") (pin "13") (pinfunction "G_13") (pintype "input"))
      (node (ref "IC5") (pin "8") (pinfunction "GND_8") (pintype "power_in"))
      (node (ref "J1") (pin "P$1") (pinfunction "GND_P$1") (pintype "bidirectional"))
      (node (ref "J1") (pin "P$2") (pinfunction "GND_P$2") (pintype "bidirectional"))
      (node (ref "MQ2-R1") (pin "1") (pinfunction "1_1") (pintype "passive"))
      (node (ref "RBIAS") (pin "2") (pinfunction "2_2") (pintype "passive"))
      (node (ref "RW5500-1") (pin "1") (pinfunction "1_1") (pintype "passive"))
      (node (ref "RW5500-2") (pin "5") (pinfunction "2_5") (pintype "passive"))
      (node (ref "RW5500-2") (pin "6") (pinfunction "2_6") (pintype "passive"))
      (node (ref "RW5500-2") (pin "7") (pinfunction "2_7") (pintype "passive"))
      (node (ref "RW5500-2") (pin "8") (pinfunction "2_8") (pintype "passive"))
      (node (ref "S1") (pin "3") (pinfunction "3_3") (pintype "passive"))
      (node (ref "S1") (pin "4") (pinfunction "4_4") (pintype "passive"))
      (node (ref "SENSOR-DHT") (pin "4") (pinfunction "4_4") (pintype "passive"))
      (node (ref "SENSOR-MQ2") (pin "HB") (pinfunction "HB_HB") (pintype "bidirectional"))
      (node (ref "SIM900-C1") (pin "-") (pinfunction "-_-") (pintype "passive"))
      (node (ref "SIM900-C2") (pin "-") (pinfunction "-_-") (pintype "passive"))
      (node (ref "SIM900-C3") (pin "2") (pinfunction "2_2") (pintype "passive"))
      (node (ref "SIM900-C4") (pin "2") (pinfunction "2_2") (pintype "passive"))
      (node (ref "SIM900-C5") (pin "2") (pinfunction "2_2") (pintype "passive"))
      (node (ref "SIM900-R6") (pin "2") (pinfunction "2_2") (pintype "passive"))
      (node (ref "SIM900-R9") (pin "2") (pinfunction "2_2") (pintype "passive"))
      (node (ref "SIM900-T1") (pin "E") (pinfunction "E_E") (pintype "passive"))
      (node (ref "SIM900-T2") (pin "E") (pinfunction "E_E") (pintype "passive"))
      (node (ref "SIM900-T3") (pin "E") (pinfunction "E_E") (pintype "passive"))
      (node (ref "SIM900-T4") (pin "E") (pinfunction "E_E") (pintype "passive"))
      (node (ref "SIM_C1") (pin "1") (pinfunction "1_1") (pintype "passive"))
      (node (ref "SIM_C2") (pin "1") (pinfunction "1_1") (pintype "passive"))
      (node (ref "SR_OUT1") (pin "2") (pinfunction "2_2") (pintype "passive"))
      (node (ref "SR_OUT2") (pin "2") (pinfunction "2_2") (pintype "passive"))
      (node (ref "STM-C1") (pin "1") (pinfunction "1_1") (pintype "passive"))
      (node (ref "STM-C10") (pin "2") (pinfunction "2_2") (pintype "passive"))
      (node (ref "STM-C11") (pin "2") (pinfunction "2_2") (pintype "passive"))
      (node (ref "STM-C12") (pin "2") (pinfunction "2_2") (pintype "passive"))
      (node (ref "STM-C13") (pin "2") (pinfunction "2_2") (pintype "passive"))
      (node (ref "STM-C2") (pin "1") (pinfunction "1_1") (pintype "passive"))
      (node (ref "STM-C3") (pin "1") (pinfunction "1_1") (pintype "passive"))
      (node (ref "STM-C8") (pin "2") (pinfunction "2_2") (pintype "passive"))
      (node (ref "STM-SWD") (pin "3") (pinfunction "3_3") (pintype "passive"))
      (node (ref "STM-USART") (pin "4") (pinfunction "4_4") (pintype "passive"))
      (node (ref "STM_CHIP") (pin "18") (pinfunction "VSS_4_18") (pintype "power_in"))
      (node (ref "STM_CHIP") (pin "31") (pinfunction "VSS_1_31") (pintype "power_in"))
      (node (ref "STM_CHIP") (pin "47") (pinfunction "VSS_2_47") (pintype "power_in"))
      (node (ref "STM_CHIP") (pin "63") (pinfunction "VSS_3_63") (pintype "power_in"))
      (node (ref "SYS-C1") (pin "2") (pinfunction "2_2") (pintype "passive"))
      (node (ref "SYS-C3") (pin "2") (pinfunction "2_2") (pintype "passive"))
      (node (ref "SYS-L1") (pin "2") (pinfunction "2_2") (pintype "passive"))
      (node (ref "U$13") (pin "LCD_GND") (pinfunction "LCD_GND_LCD_GND") (pintype "power_in"))
      (node (ref "U$13") (pin "T_CS") (pinfunction "T_CS_T_CS") (pintype "bidirectional"))
      (node (ref "U$4") (pin "3") (pinfunction "CS_3") (pintype "input"))
      (node (ref "U$5") (pin "GND") (pinfunction "GND_GND") (pintype "bidirectional"))
      (node (ref "U$5") (pin "GPIO15") (pinfunction "GPIO15_GPIO15") (pintype "bidirectional"))
      (node (ref "U$7") (pin "P$1") (pinfunction "GND_P$1") (pintype "bidirectional"))
      (node (ref "U$7") (pin "P$2") (pinfunction "GND_P$2") (pintype "bidirectional"))
      (node (ref "U$8") (pin "SHIELD_GND$1") (pinfunction "GND$1_SHIELD_GND$1") (pintype "bidirectional"))
      (node (ref "U$8") (pin "SHIELD_GND$2") (pinfunction "GND$2_SHIELD_GND$2") (pintype "bidirectional"))
      (node (ref "U$8") (pin "SIM_GND") (pinfunction "SIM_GND_SIM_GND") (pintype "bidirectional"))
      (node (ref "U2") (pin "14") (pinfunction "AGND_14") (pintype "passive"))
      (node (ref "U2") (pin "16") (pinfunction "AGND_16") (pintype "passive"))
      (node (ref "U2") (pin "19") (pinfunction "AGND_19") (pintype "passive"))
      (node (ref "U2") (pin "29") (pinfunction "GND_29") (pintype "passive"))
      (node (ref "U2") (pin "3") (pinfunction "AGND_3") (pintype "passive"))
      (node (ref "U2") (pin "48") (pinfunction "AGND_48") (pintype "passive"))
      (node (ref "U2") (pin "9") (pinfunction "AGND_9") (pintype "passive"))
      (node (ref "USB_IN") (pin "GND1") (pinfunction "GND_GND1") (pintype "bidirectional"))
      (node (ref "USB_IN") (pin "SHIELD1") (pinfunction "SHIELD_SHIELD1") (pintype "bidirectional"))
      (node (ref "USB_IN") (pin "SHIELD2") (pinfunction "SHIELD_SHIELD2") (pintype "bidirectional"))
      (node (ref "USB_IN") (pin "SHIELD3") (pinfunction "SHIELD_SHIELD3") (pintype "bidirectional"))
      (node (ref "W5500-C1") (pin "2") (pinfunction "2_2") (pintype "passive"))
      (node (ref "W5500-C10") (pin "2") (pinfunction "2_2") (pintype "passive"))
      (node (ref "W5500-C11") (pin "2") (pinfunction "2_2") (pintype "passive"))
      (node (ref "W5500-C12") (pin "-") (pinfunction "-_-") (pintype "passive"))
      (node (ref "W5500-C13") (pin "-") (pinfunction "-_-") (pintype "passive"))
      (node (ref "W5500-C2") (pin "2") (pinfunction "2_2") (pintype "passive"))
      (node (ref "W5500-C3") (pin "2") (pinfunction "2_2") (pintype "passive"))
      (node (ref "W5500-C4") (pin "2") (pinfunction "2_2") (pintype "passive"))
      (node (ref "W5500-C5") (pin "2") (pinfunction "2_2") (pintype "passive"))
      (node (ref "W5500-C6") (pin "2") (pinfunction "2_2") (pintype "passive"))
      (node (ref "W5500-C7") (pin "2") (pinfunction "2_2") (pintype "passive"))
      (node (ref "W5500-C8") (pin "2") (pinfunction "2_2") (pintype "passive"))
      (node (ref "W5500-C9") (pin "2") (pinfunction "2_2") (pintype "passive"))
      (node (ref "W5500-R11") (pin "1") (pinfunction "1_1") (pintype "passive"))
      (node (ref "W5500-R12") (pin "1") (pinfunction "1_1") (pintype "passive"))
    )
    (net (code "37") (name "DHT_DATA") (class "Default")
      (node (ref "DHT-R1") (pin "2") (pinfunction "2_2") (pintype "passive"))
      (node (ref "SENSOR-DHT") (pin "2") (pinfunction "2_2") (pintype "passive"))
      (node (ref "STM_CHIP") (pin "54") (pinfunction "PD2_54") (pintype "bidirectional"))
    )
    (net (code "38") (name "ESP_GPIO0") (class "Default")
      (node (ref "ESP-GPIO0") (pin "2") (pinfunction "2_2") (pintype "passive"))
      (node (ref "U$5") (pin "GPIO00") (pinfunction "GPIO0_GPIO00") (pintype "bidirectional"))
    )
    (net (code "39") (name "ESP_RX") (class "Default")
      (node (ref "ESP_EXT") (pin "3") (pinfunction "3_3") (pintype "passive"))
      (node (ref "JP_ESP_RX") (pin "1") (pinfunction "1_1") (pintype "passive"))
      (node (ref "U$5") (pin "RXD") (pinfunction "RXD_RXD") (pintype "bidirectional"))
    )
    (net (code "40") (name "ESP_TX") (class "Default")
      (node (ref "ESP_EXT") (pin "4") (pinfunction "4_4") (pintype "passive"))
      (node (ref "JP_ESP_TX") (pin "1") (pinfunction "1_1") (pintype "passive"))
      (node (ref "U$5") (pin "TXD") (pinfunction "TXD_TXD") (pintype "bidirectional"))
    )
    (net (code "41") (name "ETH_CS") (class "Default")
      (node (ref "STM_CHIP") (pin "33") (pinfunction "PB12_33") (pintype "bidirectional"))
      (node (ref "U2") (pin "32") (pinfunction "SCS_N_32") (pintype "passive"))
      (node (ref "W5500-R13") (pin "1") (pinfunction "1_1") (pintype "passive"))
    )
    (net (code "42") (name "ETH_MISO") (class "Default")
      (node (ref "STM_CHIP") (pin "35") (pinfunction "PB14_35") (pintype "bidirectional"))
      (node (ref "U2") (pin "34") (pinfunction "MISO_34") (pintype "passive"))
    )
    (net (code "43") (name "ETH_MOSI") (class "Default")
      (node (ref "STM_CHIP") (pin "36") (pinfunction "PB15_36") (pintype "bidirectional"))
      (node (ref "U2") (pin "35") (pinfunction "MOSI_35") (pintype "passive"))
    )
    (net (code "44") (name "ETH_RSTN") (class "Default")
      (node (ref "RW5500-3") (pin "2") (pinfunction "2_2") (pintype "passive"))
      (node (ref "STM_CHIP") (pin "37") (pinfunction "PC6_37") (pintype "bidirectional"))
      (node (ref "U2") (pin "37") (pinfunction "RST_N_37") (pintype "passive"))
    )
    (net (code "45") (name "ETH_SCK") (class "Default")
      (node (ref "STM_CHIP") (pin "34") (pinfunction "PB13_34") (pintype "bidirectional"))
      (node (ref "U2") (pin "33") (pinfunction "SCLK_33") (pintype "passive"))
    )
    (net (code "46") (name "LCD_CS") (class "Default")
      (node (ref "STM_CHIP") (pin "20") (pinfunction "PA4_20") (pintype "bidirectional"))
      (node (ref "U$13") (pin "LCD_CS") (pinfunction "LCD_CS_LCD_CS") (pintype "bidirectional"))
    )
    (net (code "47") (name "LCD_D{slash}C") (class "Default")
      (node (ref "STM_CHIP") (pin "24") (pinfunction "PC4_24") (pintype "bidirectional"))
      (node (ref "U$13") (pin "LCD_D/C") (pinfunction "LCD_D/C_LCD_D/C") (pintype "bidirectional"))
    )
    (net (code "48") (name "LCD_LED") (class "Default")
      (node (ref "LCD-R1") (pin "1") (pinfunction "1_1") (pintype "passive"))
      (node (ref "U$13") (pin "LED") (pinfunction "LCD_LED_LED") (pintype "bidirectional"))
    )
    (net (code "49") (name "LCD_MISO") (class "Default")
      (node (ref "STM_CHIP") (pin "22") (pinfunction "PA6_22") (pintype "bidirectional"))
      (node (ref "U$13") (pin "LCD_MISO") (pinfunction "LCD_MISO_LCD_MISO") (pintype "bidirectional"))
      (node (ref "U$13") (pin "SD_MISO") (pinfunction "SD_MISO_SD_MISO") (pintype "bidirectional"))
    )
    (net (code "50") (name "LCD_MOSI") (class "Default")
      (node (ref "STM_CHIP") (pin "23") (pinfunction "PA7_23") (pintype "bidirectional"))
      (node (ref "U$13") (pin "LCD_MOSI") (pinfunction "LCD_MOSI_LCD_MOSI") (pintype "bidirectional"))
      (node (ref "U$13") (pin "SD_MOSI") (pinfunction "SD_MOSI_SD_MOSI") (pintype "bidirectional"))
    )
    (net (code "51") (name "LCD_RESET") (class "Default")
      (node (ref "STM_CHIP") (pin "25") (pinfunction "PC5_25") (pintype "bidirectional"))
      (node (ref "U$13") (pin "LCD_RESET") (pinfunction "LCD_RESET_LCD_RESET") (pintype "bidirectional"))
    )
    (net (code "52") (name "LCD_SCK") (class "Default")
      (node (ref "STM_CHIP") (pin "21") (pinfunction "PA5_21") (pintype "bidirectional"))
      (node (ref "U$13") (pin "LCD_SCK") (pinfunction "LCD_SCK_LCD_SCK") (pintype "bidirectional"))
      (node (ref "U$13") (pin "SD_SCK") (pinfunction "SD_SCK_SD_SCK") (pintype "bidirectional"))
    )
    (net (code "53") (name "LINKLED") (class "Default")
      (node (ref "ETH-R5") (pin "1") (pinfunction "1_1") (pintype "passive"))
      (node (ref "U2") (pin "25") (pinfunction "LINKLED_25") (pintype "passive"))
    )
    (net (code "54") (name "MQ2_DATA") (class "Default")
      (node (ref "MQ2-R1") (pin "2") (pinfunction "2_2") (pintype "passive"))
      (node (ref "SENSOR-MQ2") (pin "B1") (pinfunction "B1_B1") (pintype "bidirectional"))
      (node (ref "SENSOR-MQ2") (pin "B2") (pinfunction "B2_B2") (pintype "bidirectional"))
      (node (ref "STM_CHIP") (pin "26") (pinfunction "PB0_26") (pintype "bidirectional"))
    )
    (net (code "55") (name "Net-(ADE-R1-Pad1)") (class "Default")
      (node (ref "ADE-R1") (pin "1") (pinfunction "1_1") (pintype "passive"))
      (node (ref "RTO1") (pin "2") (pinfunction "2_2") (pintype "passive"))
      (node (ref "U$9") (pin "OA") (pinfunction "OA_OA") (pintype "bidirectional"))
    )
    (net (code "56") (name "Net-(ADE-R2-Pad1)") (class "Default")
      (node (ref "ADE-R2") (pin "1") (pinfunction "1_1") (pintype "passive"))
      (node (ref "RTO2") (pin "2") (pinfunction "2_2") (pintype "passive"))
      (node (ref "U$10") (pin "OA") (pinfunction "OA_OA") (pintype "bidirectional"))
    )
    (net (code "57") (name "Net-(ADE-R3-Pad1)") (class "Default")
      (node (ref "ADE-R3") (pin "1") (pinfunction "1_1") (pintype "passive"))
      (node (ref "RTO3") (pin "2") (pinfunction "2_2") (pintype "passive"))
      (node (ref "U$11") (pin "OA") (pinfunction "OA_OA") (pintype "bidirectional"))
    )
    (net (code "58") (name "Net-(ADE-R7-Pad1)") (class "Default")
      (node (ref "ADE-R7") (pin "1") (pinfunction "1_1") (pintype "passive"))
      (node (ref "RTO1") (pin "1") (pinfunction "1_1") (pintype "passive"))
      (node (ref "RTO2") (pin "1") (pinfunction "1_1") (pintype "passive"))
      (node (ref "RTO3") (pin "1") (pinfunction "1_1") (pintype "passive"))
      (node (ref "U$10") (pin "OB") (pinfunction "OB_OB") (pintype "bidirectional"))
      (node (ref "U$11") (pin "OB") (pinfunction "OB_OB") (pintype "bidirectional"))
      (node (ref "U$9") (pin "OB") (pinfunction "OB_OB") (pintype "bidirectional"))
    )
    (net (code "59") (name "Net-(ADE-R8-Pad2)") (class "Default")
      (node (ref "ADE-R8") (pin "2") (pinfunction "2_2") (pintype "passive"))
      (node (ref "ADE-R9") (pin "1") (pinfunction "1_1") (pintype "passive"))
      (node (ref "JP2") (pin "SLEEVE") (pinfunction "SLEEVE_SLEEVE") (pintype "bidirectional"))
    )
    (net (code "60") (name "Net-(ADE-R11-Pad2)") (class "Default")
      (node (ref "ADE-R11") (pin "2") (pinfunction "2_2") (pintype "passive"))
      (node (ref "ADE-R12") (pin "1") (pinfunction "1_1") (pintype "passive"))
      (node (ref "JP3") (pin "SLEEVE") (pinfunction "SLEEVE_SLEEVE") (pintype "bidirectional"))
    )
    (net (code "61") (name "Net-(ADE-R14-Pad2)") (class "Default")
      (node (ref "ADE-R14") (pin "2") (pinfunction "2_2") (pintype "passive"))
      (node (ref "ADE-R15") (pin "1") (pinfunction "1_1") (pintype "passive"))
      (node (ref "JP4") (pin "SLEEVE") (pinfunction "SLEEVE_SLEEVE") (pintype "bidirectional"))
    )
    (net (code "62") (name "Net-(B1-ANT)") (class "Default")
      (node (ref "B1") (pin "1") (pinfunction "ANT_1") (pintype "bidirectional"))
      (node (ref "J1") (pin "P$3") (pinfunction "SIGNAL_P$3") (pintype "bidirectional"))
    )
    (net (code "63") (name "Net-(B1-BAL_N)") (class "Default")
      (node (ref "B1") (pin "3") (pinfunction "BAL_N_3") (pintype "bidirectional"))
      (node (ref "U$4") (pin "19") (pinfunction "RF-N_19") (pintype "bidirectional"))
    )
    (net (code "64") (name "Net-(B1-BAL_P)") (class "Default")
      (node (ref "B1") (pin "4") (pinfunction "BAL_P_4") (pintype "bidirectional"))
      (node (ref "U$4") (pin "17") (pinfunction "RF-P_17") (pintype "bidirectional"))
    )
    (net (code "65") (name "Net-(ETHERNET-LED1_K)") (class "Default")
      (node (ref "ETH-R4") (pin "2") (pinfunction "2_2") (pintype "passive"))
      (node (ref "ETHERNET") (pin "10") (pinfunction "LED1_K_10") (pintype "bidirectional"))
    )
    (net (code "66") (name "Net-(ETHERNET-LED2_K)") (class "Default")
      (node (ref "ETH-R5") (pin "2") (pinfunction "2_2") (pintype "passive"))
      (node (ref "ETHERNET") (pin "11") (pinfunction "LED2_K_11") (pintype "bidirectional"))
    )
    (net (code "67") (name "Net-(ETHERNET-RCT)") (class "Default")
      (node (ref "ETH-C3") (pin "2") (pinfunction "2_2") (pintype "passive"))
      (node (ref "ETH-R6") (pin "1") (pinfunction "1_1") (pintype "passive"))
      (node (ref "ETH-R7") (pin "2") (pinfunction "2_2") (pintype "passive"))
      (node (ref "ETHERNET") (pin "6") (pinfunction "RCT_6") (pintype "bidirectional"))
    )
    (net (code "68") (name "Net-(ETHERNET-RX+)") (class "Default")
      (node (ref "ETH-C2") (pin "1") (pinfunction "1_1") (pintype "passive"))
      (node (ref "ETHERNET") (pin "7") (pinfunction "RX+_7") (pintype "bidirectional"))
    )
    (net (code "69") (name "Net-(ETHERNET-RX-)") (class "Default")
      (node (ref "ETH-C4") (pin "1") (pinfunction "1_1") (pintype "passive"))
      (node (ref "ETHERNET") (pin "8") (pinfunction "RX-_8") (pintype "bidirectional"))
    )
    (net (code "70") (name "Net-(ETHERNET-TCT)") (class "Default")
      (node (ref "ETH-C1") (pin "2") (pinfunction "2_2") (pintype "passive"))
      (node (ref "ETH-R3") (pin "1") (pinfunction "1_1") (pintype "passive"))
      (node (ref "ETHERNET") (pin "3") (pinfunction "TCT_3") (pintype "bidirectional"))
    )
    (net (code "71") (name "Net-(IC1-RF_ANT)") (class "Default")
      (node (ref "IC1") (pin "P$60") (pinfunction "RF_ANT_P$60") (pintype "bidirectional"))
      (node (ref "U$7") (pin "P$3") (pinfunction "SIGNAL_P$3") (pintype "bidirectional"))
    )
    (net (code "72") (name "Net-(IC1-SIM_CLK)") (class "Default")
      (node (ref "IC1") (pin "P$32") (pinfunction "SIM_CLK_P$32") (pintype "bidirectional"))
      (node (ref "SIM900-R2") (pin "1") (pinfunction "1_1") (pintype "passive"))
    )
    (net (code "73") (name "Net-(IC1-SIM_DATA)") (class "Default")
      (node (ref "IC1") (pin "P$31") (pinfunction "SIM_DATA_P$31") (pintype "bidirectional"))
      (node (ref "SIM900-R3") (pin "1") (pinfunction "1_1") (pintype "passive"))
    )
    (net (code "74") (name "Net-(IC1-SIM_RST)") (class "Default")
      (node (ref "IC1") (pin "P$33") (pinfunction "SIM_RST_P$33") (pintype "bidirectional"))
      (node (ref "SIM900-R1") (pin "1") (pinfunction "1_1") (pintype "passive"))
    )
    (net (code "75") (name "Net-(IC1-VBAT1)") (class "Default")
      (node (ref "IC1") (pin "P$55") (pinfunction "VBAT1_P$55") (pintype "power_in"))
      (node (ref "IC1") (pin "P$56") (pinfunction "VBAT2_P$56") (pintype "power_in"))
      (node (ref "IC1") (pin "P$57") (pinfunction "VBAT3_P$57") (pintype "power_in"))
      (node (ref "SIM900-C1") (pin "+") (pinfunction "+_+") (pintype "passive"))
      (node (ref "SIM900-C2") (pin "+") (pinfunction "+_+") (pintype "passive"))
      (node (ref "SYS-L2") (pin "1") (pinfunction "1_1") (pintype "passive"))
    )
    (net (code "76") (name "Net-(IC1-VRTC)") (class "Default")
      (node (ref "IC1") (pin "P$26") (pinfunction "VRTC_P$26") (pintype "power_in"))
      (node (ref "SIM900-C3") (pin "1") (pinfunction "1_1") (pintype "passive"))
    )
    (net (code "77") (name "Net-(IC4A-CLKIN)") (class "Default")
      (node (ref "ADE-C3") (pin "1") (pinfunction "1_1") (pintype "passive"))
      (node (ref "ADE-XTAL") (pin "1") (pinfunction "1_1") (pintype "passive"))
      (node (ref "IC4") (pin "19") (pinfunction "CLKIN_19") (pintype "input"))
    )
    (net (code "78") (name "Net-(IC4A-CLKOUT)") (class "Default")
      (node (ref "ADE-C4") (pin "1") (pinfunction "1_1") (pintype "passive"))
      (node (ref "ADE-XTAL") (pin "2") (pinfunction "2_2") (pintype "passive"))
      (node (ref "IC4") (pin "20") (pinfunction "CLKOUT_20") (pintype "output"))
    )
    (net (code "79") (name "Net-(IC4C-IN)") (class "Default")
      (node (ref "ADE-C12") (pin "1") (pinfunction "1_1") (pintype "passive"))
      (node (ref "ADE-R10") (pin "2") (pinfunction "2_2") (pintype "passive"))
      (node (ref "IC4") (pin "6") (pinfunction "IN_6") (pintype "input"))
    )
    (net (code "80") (name "Net-(IC4C-IP)") (class "Default")
      (node (ref "ADE-C11") (pin "1") (pinfunction "1_1") (pintype "passive"))
      (node (ref "ADE-R9") (pin "2") (pinfunction "2_2") (pintype "passive"))
      (node (ref "IC4") (pin "5") (pinfunction "IP_5") (pintype "input"))
    )
    (net (code "81") (name "Net-(IC4D-IN)") (class "Default")
      (node (ref "ADE-C14") (pin "1") (pinfunction "1_1") (pintype "passive"))
      (node (ref "ADE-R13") (pin "2") (pinfunction "2_2") (pintype "passive"))
      (node (ref "IC4") (pin "8") (pinfunction "IN_8") (pintype "input"))
    )
    (net (code "82") (name "Net-(IC4D-IP)") (class "Default")
      (node (ref "ADE-C13") (pin "1") (pinfunction "1_1") (pintype "passive"))
      (node (ref "ADE-R12") (pin "2") (pinfunction "2_2") (pintype "passive"))
      (node (ref "IC4") (pin "7") (pinfunction "IP_7") (pintype "input"))
    )
    (net (code "83") (name "Net-(IC4E-IN)") (class "Default")
      (node (ref "ADE-C16") (pin "1") (pinfunction "1_1") (pintype "passive"))
      (node (ref "ADE-R16") (pin "2") (pinfunction "2_2") (pintype "passive"))
      (node (ref "IC4") (pin "10") (pinfunction "IN_10") (pintype "input"))
    )
    (net (code "84") (name "Net-(IC4E-IP)") (class "Default")
      (node (ref "ADE-C15") (pin "1") (pinfunction "1_1") (pintype "passive"))
      (node (ref "ADE-R15") (pin "2") (pinfunction "2_2") (pintype "passive"))
      (node (ref "IC4") (pin "9") (pinfunction "IP_9") (pintype "input"))
    )
    (net (code "85") (name "Net-(IC4F-REF)") (class "Default")
      (node (ref "ADE-C1") (pin "1") (pinfunction "1_1") (pintype "passive"))
      (node (ref "ADE-C2") (pin "1") (pinfunction "1_1") (pintype "passive"))
      (node (ref "IC4") (pin "12") (pinfunction "REF_12") (pintype "bidirectional"))
    )
    (net (code "86") (name "Net-(IC4G-VAP)") (class "Default")
      (node (ref "ADE-C7") (pin "1") (pinfunction "1_1") (pintype "passive"))
      (node (ref "ADE-R1") (pin "2") (pinfunction "2_2") (pintype "passive"))
      (node (ref "ADE-R4") (pin "2") (pinfunction "2_2") (pintype "passive"))
      (node (ref "IC4") (pin "16") (pinfunction "VAP_16") (pintype "input"))
    )
    (net (code "87") (name "Net-(IC4G-VBP)") (class "Default")
      (node (ref "ADE-C8") (pin "1") (pinfunction "1_1") (pintype "passive"))
      (node (ref "ADE-R2") (pin "2") (pinfunction "2_2") (pintype "passive"))
      (node (ref "ADE-R5") (pin "2") (pinfunction "2_2") (pintype "passive"))
      (node (ref "IC4") (pin "15") (pinfunction "VBP_15") (pintype "input"))
    )
    (net (code "88") (name "Net-(IC4G-VCP)") (class "Default")
      (node (ref "ADE-C9") (pin "1") (pinfunction "1_1") (pintype "passive"))
      (node (ref "ADE-R3") (pin "2") (pinfunction "2_2") (pintype "passive"))
      (node (ref "ADE-R6") (pin "2") (pinfunction "2_2") (pintype "passive"))
      (node (ref "IC4") (pin "14") (pinfunction "VCP_14") (pintype "input"))
    )
    (net (code "89") (name "Net-(IC4G-VN)") (class "Default")
      (node (ref "ADE-C10") (pin "1") (pinfunction "1_1") (pintype "passive"))
      (node (ref "ADE-R7") (pin "2") (pinfunction "2_2") (pintype "passive"))
      (node (ref "IC4") (pin "13") (pinfunction "VN_13") (pintype "input"))
    )
    (net (code "90") (name "Net-(JP2-LEFT)") (class "Default")
      (node (ref "ADE-R10") (pin "1") (pinfunction "1_1") (pintype "passive"))
      (node (ref "ADE-R8") (pin "1") (pinfunction "1_1") (pintype "passive"))
      (node (ref "JP2") (pin "RING") (pinfunction "RIGHT_RING") (pintype "bidirectional"))
      (node (ref "JP2") (pin "TIP") (pinfunction "LEFT_TIP") (pintype "bidirectional"))
    )
    (net (code "91") (name "Net-(JP3-LEFT)") (class "Default")
      (node (ref "ADE-R11") (pin "1") (pinfunction "1_1") (pintype "passive"))
      (node (ref "ADE-R13") (pin "1") (pinfunction "1_1") (pintype "passive"))
      (node (ref "JP3") (pin "RING") (pinfunction "RIGHT_RING") (pintype "bidirectional"))
      (node (ref "JP3") (pin "TIP") (pinfunction "LEFT_TIP") (pintype "bidirectional"))
    )
    (net (code "92") (name "Net-(JP4-LEFT)") (class "Default")
      (node (ref "ADE-R14") (pin "1") (pinfunction "1_1") (pintype "passive"))
      (node (ref "ADE-R16") (pin "1") (pinfunction "1_1") (pintype "passive"))
      (node (ref "JP4") (pin "RING") (pinfunction "RIGHT_RING") (pintype "bidirectional"))
      (node (ref "JP4") (pin "TIP") (pinfunction "LEFT_TIP") (pintype "bidirectional"))
    )
    (net (code "93") (name "Net-(OK1A-A)") (class "Default")
      (node (ref "OK1") (pin "1") (pinfunction "A_1") (pintype "passive"))
      (node (ref "R_CH3") (pin "2") (pinfunction "2_2") (pintype "passive"))
    )
    (net (code "94") (name "Net-(OK1B-A)") (class "Default")
      (node (ref "OK1") (pin "3") (pinfunction "A_3") (pintype "passive"))
      (node (ref "R_CH4") (pin "2") (pinfunction "2_2") (pintype "passive"))
    )
    (net (code "95") (name "Net-(OK2A-A)") (class "Default")
      (node (ref "OK2") (pin "1") (pinfunction "A_1") (pintype "passive"))
      (node (ref "R_CH1") (pin "2") (pinfunction "2_2") (pintype "passive"))
    )
    (net (code "96") (name "Net-(OK2B-A)") (class "Default")
      (node (ref "OK2") (pin "3") (pinfunction "A_3") (pintype "passive"))
      (node (ref "R_CH2") (pin "2") (pinfunction "2_2") (pintype "passive"))
    )
    (net (code "97") (name "Net-(RT1-Pad2)") (class "Default")
      (node (ref "RT1") (pin "2") (pinfunction "2_2") (pintype "passive"))
      (node (ref "U$9") (pin "IA") (pinfunction "IA_IA") (pintype "bidirectional"))
    )
    (net (code "98") (name "Net-(RT2-Pad2)") (class "Default")
      (node (ref "RT2") (pin "2") (pinfunction "2_2") (pintype "passive"))
      (node (ref "U$10") (pin "IA") (pinfunction "IA_IA") (pintype "bidirectional"))
    )
    (net (code "99") (name "Net-(RT3-Pad2)") (class "Default")
      (node (ref "RT3") (pin "2") (pinfunction "2_2") (pintype "passive"))
      (node (ref "U$11") (pin "IA") (pinfunction "IA_IA") (pintype "bidirectional"))
    )
    (net (code "100") (name "Net-(RW5500-1A-2)") (class "Default")
      (node (ref "RW5500-1") (pin "8") (pinfunction "2_8") (pintype "passive"))
      (node (ref "U2") (pin "42") (pinfunction "RSVD_42") (pintype "passive"))
    )
    (net (code "101") (name "Net-(RW5500-1B-2)") (class "Default")
      (node (ref "RW5500-1") (pin "7") (pinfunction "2_7") (pintype "passive"))
      (node (ref "U2") (pin "43") (pinfunction "PMODE2_43") (pintype "passive"))
    )
    (net (code "102") (name "Net-(RW5500-1C-2)") (class "Default")
      (node (ref "RW5500-1") (pin "6") (pinfunction "2_6") (pintype "passive"))
      (node (ref "U2") (pin "44") (pinfunction "PMODE1_44") (pintype "passive"))
    )
    (net (code "103") (name "Net-(RW5500-1D-2)") (class "Default")
      (node (ref "RW5500-1") (pin "5") (pinfunction "2_5") (pintype "passive"))
      (node (ref "U2") (pin "45") (pinfunction "PMODE0_45") (pintype "passive"))
    )
    (net (code "104") (name "Net-(RW5500-2-Pad1)") (class "Default")
      (node (ref "RW5500-2") (pin "1") (pinfunction "1_1") (pintype "passive"))
      (node (ref "U2") (pin "41") (pinfunction "RSVD_41") (pintype "passive"))
    )
    (net (code "105") (name "Net-(RW5500-2B-1)") (class "Default")
      (node (ref "RW5500-2") (pin "2") (pinfunction "1_2") (pintype "passive"))
      (node (ref "U2") (pin "40") (pinfunction "RSVD_40") (pintype "passive"))
    )
    (net (code "106") (name "Net-(RW5500-2C-1)") (class "Default")
      (node (ref "RW5500-2") (pin "3") (pinfunction "1_3") (pintype "passive"))
      (node (ref "U2") (pin "39") (pinfunction "RSVD_39") (pintype "passive"))
    )
    (net (code "107") (name "Net-(RW5500-2D-1)") (class "Default")
      (node (ref "RW5500-2") (pin "4") (pinfunction "1_4") (pintype "passive"))
      (node (ref "U2") (pin "38") (pinfunction "RSVD_38") (pintype "passive"))
    )
    (net (code "108") (name "Net-(SIM900-LED1-PadA)") (class "Default")
      (node (ref "SIM900-LED1") (pin "A") (pinfunction "A_A") (pintype "passive"))
      (node (ref "SIM900-R4") (pin "1") (pinfunction "1_1") (pintype "passive"))
    )
    (net (code "109") (name "Net-(SIM900-LED1-PadC)") (class "Default")
      (node (ref "SIM900-LED1") (pin "C") (pinfunction "C_C") (pintype "passive"))
      (node (ref "SIM900-T1") (pin "C") (pinfunction "C_C") (pintype "passive"))
    )
    (net (code "110") (name "Net-(SIM900-LED2-PadA)") (class "Default")
      (node (ref "SIM900-LED2") (pin "A") (pinfunction "A_A") (pintype "passive"))
      (node (ref "SIM900-R7") (pin "1") (pinfunction "1_1") (pintype "passive"))
    )
    (net (code "111") (name "Net-(SIM900-LED2-PadC)") (class "Default")
      (node (ref "SIM900-LED2") (pin "C") (pinfunction "C_C") (pintype "passive"))
      (node (ref "SIM900-T2") (pin "C") (pinfunction "C_C") (pintype "passive"))
    )
    (net (code "112") (name "Net-(SIM900-R5-Pad1)") (class "Default")
      (node (ref "SIM900-R5") (pin "1") (pinfunction "1_1") (pintype "passive"))
      (node (ref "SIM900-R6") (pin "1") (pinfunction "1_1") (pintype "passive"))
      (node (ref "SIM900-T1") (pin "B") (pinfunction "B_B") (pintype "passive"))
    )
    (net (code "113") (name "Net-(SIM900-R8-Pad1)") (class "Default")
      (node (ref "SIM900-R8") (pin "1") (pinfunction "1_1") (pintype "passive"))
      (node (ref "SIM900-R9") (pin "1") (pinfunction "1_1") (pintype "passive"))
      (node (ref "SIM900-T2") (pin "B") (pinfunction "B_B") (pintype "passive"))
    )
    (net (code "114") (name "Net-(SIM900-R10-Pad2)") (class "Default")
      (node (ref "SIM900-R10") (pin "2") (pinfunction "2_2") (pintype "passive"))
      (node (ref "SIM900-T3") (pin "B") (pinfunction "B_B") (pintype "passive"))
    )
    (net (code "115") (name "Net-(SIM900-R11-Pad2)") (class "Default")
      (node (ref "SIM900-R11") (pin "2") (pinfunction "2_2") (pintype "passive"))
      (node (ref "SIM900-T4") (pin "B") (pinfunction "B_B") (pintype "passive"))
    )
    (net (code "116") (name "Net-(STM_CHIP-PA2)") (class "Default")
      (node (ref "JP_ESP_RX") (pin "2") (pinfunction "2_2") (pintype "passive"))
      (node (ref "STM_CHIP") (pin "16") (pinfunction "PA2_16") (pintype "bidirectional"))
    )
    (net (code "117") (name "Net-(STM_CHIP-PA3)") (class "Default")
      (node (ref "JP_ESP_TX") (pin "2") (pinfunction "2_2") (pintype "passive"))
      (node (ref "STM_CHIP") (pin "17") (pinfunction "PA3_17") (pintype "bidirectional"))
    )
    (net (code "118") (name "Net-(STM_CHIP-PC14-OSC32_IN)") (class "Default")
      (node (ref "STM-C2") (pin "2") (pinfunction "2_2") (pintype "passive"))
      (node (ref "STM-XTAL") (pin "2") (pinfunction "2_2") (pintype "passive"))
      (node (ref "STM_CHIP") (pin "3") (pinfunction "PC14-OSC32_IN_3") (pintype "bidirectional"))
    )
    (net (code "119") (name "Net-(STM_CHIP-PC15-OSC32_OUT)") (class "Default")
      (node (ref "STM-C3") (pin "2") (pinfunction "2_2") (pintype "passive"))
      (node (ref "STM-XTAL") (pin "1") (pinfunction "1_1") (pintype "passive"))
      (node (ref "STM_CHIP") (pin "4") (pinfunction "PC15-OSC32_OUT_4") (pintype "bidirectional"))
    )
    (net (code "120") (name "Net-(U$4B-DCOUPL)") (class "Default")
      (node (ref "CC_DCOUP") (pin "1") (pinfunction "1_1") (pintype "passive"))
      (node (ref "U$4") (pin "27") (pinfunction "DCOUPL_27") (pintype "power_in"))
    )
    (net (code "121") (name "Net-(U$4C-RBIAS)") (class "Default")
      (node (ref "RBIAS") (pin "1") (pinfunction "1_1") (pintype "passive"))
      (node (ref "U$4") (pin "23") (pinfunction "RBIAS_23") (pintype "bidirectional"))
    )
    (net (code "122") (name "Net-(U$4C-VREG-EN)") (class "Default")
      (node (ref "R_VREG") (pin "1") (pinfunction "1_1") (pintype "passive"))
      (node (ref "U$4") (pin "26") (pinfunction "VREG-EN_26") (pintype "input"))
    )
    (net (code "123") (name "Net-(U$4C-XOSC32M-Q1)") (class "Default")
      (node (ref "CC_CX1") (pin "1") (pinfunction "1_1") (pintype "passive"))
      (node (ref "U$4") (pin "13") (pinfunction "XOSC32M-Q1_13") (pintype "input"))
      (node (ref "X1") (pin "1") (pinfunction "1_1") (pintype "bidirectional"))
    )
    (net (code "124") (name "Net-(U$4C-XOSC32M-Q2)") (class "Default")
      (node (ref "CC_CX2") (pin "1") (pinfunction "1_1") (pintype "passive"))
      (node (ref "U$4") (pin "12") (pinfunction "XOSC32M-Q2_12") (pintype "output"))
      (node (ref "X1") (pin "3") (pinfunction "2_3") (pintype "bidirectional"))
    )
    (net (code "125") (name "Net-(U$12-P$1)") (class "Default")
      (node (ref "RT1") (pin "1") (pinfunction "1_1") (pintype "passive"))
      (node (ref "U$12") (pin "P1") (pinfunction "P$1_P1") (pintype "bidirectional"))
    )
    (net (code "126") (name "Net-(U$12-P$2)") (class "Default")
      (node (ref "RT2") (pin "1") (pinfunction "1_1") (pintype "passive"))
      (node (ref "U$12") (pin "P2") (pinfunction "P$2_P2") (pintype "bidirectional"))
    )
    (net (code "127") (name "Net-(U$12-P$3)") (class "Default")
      (node (ref "RT3") (pin "1") (pinfunction "1_1") (pintype "passive"))
      (node (ref "U$12") (pin "P3") (pinfunction "P$3_P3") (pintype "bidirectional"))
    )
    (net (code "128") (name "Net-(U$12-P$4)") (class "Default")
      (node (ref "U$10") (pin "IB") (pinfunction "IB_IB") (pintype "bidirectional"))
      (node (ref "U$11") (pin "IB") (pinfunction "IB_IB") (pintype "bidirectional"))
      (node (ref "U$12") (pin "P4") (pinfunction "P$4_P4") (pintype "bidirectional"))
      (node (ref "U$9") (pin "IB") (pinfunction "IB_IB") (pintype "bidirectional"))
    )
    (net (code "129") (name "Net-(U2-1V2O)") (class "Default")
      (node (ref "U2") (pin "22") (pinfunction "1V2O_22") (pintype "passive"))
      (node (ref "W5500-C4") (pin "1") (pinfunction "1_1") (pintype "passive"))
    )
    (net (code "130") (name "Net-(U2-EXRES1)") (class "Default")
      (node (ref "U2") (pin "10") (pinfunction "EXRES1_10") (pintype "passive"))
      (node (ref "W5500-R12") (pin "2") (pinfunction "2_2") (pintype "passive"))
    )
    (net (code "131") (name "Net-(U2-RSVD-Pad23)") (class "Default")
      (node (ref "U2") (pin "23") (pinfunction "RSVD_23") (pintype "passive"))
      (node (ref "W5500-R11") (pin "2") (pinfunction "2_2") (pintype "passive"))
    )
    (net (code "132") (name "Net-(U2-TOCAP)") (class "Default")
      (node (ref "U2") (pin "20") (pinfunction "TOCAP_20") (pintype "passive"))
      (node (ref "W5500-C3") (pin "1") (pinfunction "1_1") (pintype "passive"))
    )
    (net (code "133") (name "Net-(U2-XI{slash}CLKIN)") (class "Default")
      (node (ref "U2") (pin "30") (pinfunction "XI/CLKIN_30") (pintype "passive"))
      (node (ref "W5500-C1") (pin "1") (pinfunction "1_1") (pintype "passive"))
      (node (ref "W5500-R10") (pin "1") (pinfunction "1_1") (pintype "passive"))
      (node (ref "W5500-XTAL") (pin "1") (pinfunction "1_1") (pintype "passive"))
    )
    (net (code "134") (name "Net-(U2-XO)") (class "Default")
      (node (ref "U2") (pin "31") (pinfunction "XO_31") (pintype "passive"))
      (node (ref "W5500-C2") (pin "1") (pinfunction "1_1") (pintype "passive"))
      (node (ref "W5500-R10") (pin "2") (pinfunction "2_2") (pintype "passive"))
      (node (ref "W5500-XTAL") (pin "2") (pinfunction "2_2") (pintype "passive"))
    )
    (net (code "135") (name "Q1") (class "Default")
      (node (ref "IC2") (pin "15") (pinfunction "QA_15") (pintype "tri_state"))
      (node (ref "SR_OUT1") (pin "3") (pinfunction "3_3") (pintype "passive"))
    )
    (net (code "136") (name "Q2") (class "Default")
      (node (ref "IC2") (pin "1") (pinfunction "QB_1") (pintype "tri_state"))
      (node (ref "SR_OUT1") (pin "4") (pinfunction "4_4") (pintype "passive"))
    )
    (net (code "137") (name "Q3") (class "Default")
      (node (ref "IC2") (pin "2") (pinfunction "QC_2") (pintype "tri_state"))
      (node (ref "SR_OUT1") (pin "5") (pinfunction "5_5") (pintype "passive"))
    )
    (net (code "138") (name "Q4") (class "Default")
      (node (ref "IC2") (pin "3") (pinfunction "QD_3") (pintype "tri_state"))
      (node (ref "SR_OUT1") (pin "6") (pinfunction "6_6") (pintype "passive"))
    )
    (net (code "139") (name "Q5") (class "Default")
      (node (ref "IC2") (pin "4") (pinfunction "QE_4") (pintype "tri_state"))
      (node (ref "SR_OUT1") (pin "7") (pinfunction "7_7") (pintype "passive"))
    )
    (net (code "140") (name "Q6") (class "Default")
      (node (ref "IC2") (pin "5") (pinfunction "QF_5") (pintype "tri_state"))
      (node (ref "SR_OUT1") (pin "8") (pinfunction "8_8") (pintype "passive"))
    )
    (net (code "141") (name "Q7") (class "Default")
      (node (ref "IC2") (pin "6") (pinfunction "QG_6") (pintype "tri_state"))
      (node (ref "SR_OUT1") (pin "9") (pinfunction "9_9") (pintype "passive"))
    )
    (net (code "142") (name "Q8") (class "Default")
      (node (ref "IC2") (pin "7") (pinfunction "QH_7") (pintype "tri_state"))
      (node (ref "SR_OUT1") (pin "10") (pinfunction "10_10") (pintype "passive"))
    )
    (net (code "143") (name "Q9") (class "Default")
      (node (ref "IC3") (pin "15") (pinfunction "QA_15") (pintype "tri_state"))
      (node (ref "SR_OUT2") (pin "3") (pinfunction "3_3") (pintype "passive"))
    )
    (net (code "144") (name "Q10") (class "Default")
      (node (ref "IC3") (pin "1") (pinfunction "QB_1") (pintype "tri_state"))
      (node (ref "SR_OUT2") (pin "4") (pinfunction "4_4") (pintype "passive"))
    )
    (net (code "145") (name "Q11") (class "Default")
      (node (ref "IC3") (pin "2") (pinfunction "QC_2") (pintype "tri_state"))
      (node (ref "SR_OUT2") (pin "5") (pinfunction "5_5") (pintype "passive"))
    )
    (net (code "146") (name "Q12") (class "Default")
      (node (ref "IC3") (pin "3") (pinfunction "QD_3") (pintype "tri_state"))
      (node (ref "SR_OUT2") (pin "6") (pinfunction "6_6") (pintype "passive"))
    )
    (net (code "147") (name "Q13") (class "Default")
      (node (ref "IC3") (pin "4") (pinfunction "QE_4") (pintype "tri_state"))
      (node (ref "SR_OUT2") (pin "7") (pinfunction "7_7") (pintype "passive"))
    )
    (net (code "148") (name "Q14") (class "Default")
      (node (ref "IC3") (pin "5") (pinfunction "QF_5") (pintype "tri_state"))
      (node (ref "SR_OUT2") (pin "8") (pinfunction "8_8") (pintype "passive"))
    )
    (net (code "149") (name "Q15") (class "Default")
      (node (ref "IC3") (pin "6") (pinfunction "QG_6") (pintype "tri_state"))
      (node (ref "SR_OUT2") (pin "9") (pinfunction "9_9") (pintype "passive"))
    )
    (net (code "150") (name "Q16") (class "Default")
      (node (ref "IC3") (pin "7") (pinfunction "QH_7") (pintype "tri_state"))
      (node (ref "SR_OUT2") (pin "10") (pinfunction "10_10") (pintype "passive"))
    )
    (net (code "151") (name "QS") (class "Default")
      (node (ref "IC2") (pin "9") (pinfunction "QH*_9") (pintype "tri_state"))
      (node (ref "IC3") (pin "14") (pinfunction "SER_14") (pintype "input"))
    )
    (net (code "152") (name "QS2") (class "Default")
      (node (ref "IC3") (pin "9") (pinfunction "QH*_9") (pintype "tri_state"))
      (node (ref "IC5") (pin "14") (pinfunction "SER_14") (pintype "input"))
    )
    (net (code "153") (name "RXN") (class "Default")
      (node (ref "ETH-C4") (pin "2") (pinfunction "2_2") (pintype "passive"))
      (node (ref "ETH-R7") (pin "1") (pinfunction "1_1") (pintype "passive"))
      (node (ref "U2") (pin "5") (pinfunction "RXN_5") (pintype "passive"))
    )
    (net (code "154") (name "RXP") (class "Default")
      (node (ref "ETH-C2") (pin "2") (pinfunction "2_2") (pintype "passive"))
      (node (ref "ETH-R6") (pin "2") (pinfunction "2_2") (pintype "passive"))
      (node (ref "U2") (pin "6") (pinfunction "RXP_6") (pintype "passive"))
    )
    (net (code "155") (name "SD_CS") (class "Default")
      (node (ref "STM_CHIP") (pin "55") (pinfunction "PB3_55") (pintype "bidirectional"))
      (node (ref "U$13") (pin "SD_CS") (pinfunction "SD_CS_SD_CS") (pintype "bidirectional"))
    )
    (net (code "156") (name "SERIAL_RX") (class "Default")
      (node (ref "STM-USART") (pin "3") (pinfunction "3_3") (pintype "passive"))
      (node (ref "STM_CHIP") (pin "43") (pinfunction "PA10_43") (pintype "bidirectional"))
    )
    (net (code "157") (name "SERIAL_TX") (class "Default")
      (node (ref "STM-USART") (pin "2") (pinfunction "2_2") (pintype "passive"))
      (node (ref "STM_CHIP") (pin "42") (pinfunction "PA9_42") (pintype "bidirectional"))
    )
    (net (code "158") (name "SIM900_PWRKEY") (class "Default")
      (node (ref "IC1") (pin "P$1") (pinfunction "PWRKEY_P$1") (pintype "power_in"))
      (node (ref "SIM900-T3") (pin "C") (pinfunction "C_C") (pintype "passive"))
    )
    (net (code "159") (name "SIM900_RESET") (class "Default")
      (node (ref "IC1") (pin "P$16") (pinfunction "NRESET_P$16") (pintype "bidirectional"))
      (node (ref "SIM900-T4") (pin "C") (pinfunction "C_C") (pintype "passive"))
    )
    (net (code "160") (name "SIM_NETLIGHT") (class "Default")
      (node (ref "IC1") (pin "P$52") (pinfunction "NETLIGHT_P$52") (pintype "bidirectional"))
      (node (ref "SIM900-R8") (pin "2") (pinfunction "2_2") (pintype "passive"))
    )
    (net (code "161") (name "SIM_PWRKEY") (class "Default")
      (node (ref "SIM900-R10") (pin "1") (pinfunction "1_1") (pintype "passive"))
      (node (ref "STM_CHIP") (pin "41") (pinfunction "PA8_41") (pintype "bidirectional"))
    )
    (net (code "162") (name "SIM_RESET") (class "Default")
      (node (ref "SIM900-R11") (pin "1") (pinfunction "1_1") (pintype "passive"))
    )
    (net (code "163") (name "SIM_RX") (class "Default")
      (node (ref "IC1") (pin "P$10") (pinfunction "RXD_P$10") (pintype "input"))
      (node (ref "STM_CHIP") (pin "51") (pinfunction "PC10_51") (pintype "bidirectional"))
    )
    (net (code "164") (name "SIM_STATUS") (class "Default")
      (node (ref "IC1") (pin "P$66") (pinfunction "STATUS_P$66") (pintype "bidirectional"))
      (node (ref "SIM900-R5") (pin "2") (pinfunction "2_2") (pintype "passive"))
    )
    (net (code "165") (name "SIM_TX") (class "Default")
      (node (ref "IC1") (pin "P$9") (pinfunction "TXD_P$9") (pintype "output"))
      (node (ref "STM_CHIP") (pin "50") (pinfunction "PA15_50") (pintype "bidirectional"))
    )
    (net (code "166") (name "SR_DS") (class "Default")
      (node (ref "IC2") (pin "14") (pinfunction "SER_14") (pintype "input"))
      (node (ref "STM_CHIP") (pin "8") (pinfunction "PC0_8") (pintype "bidirectional"))
    )
    (net (code "167") (name "SR_RST") (class "Default")
      (node (ref "IC2") (pin "10") (pinfunction "SCL_10") (pintype "input"))
      (node (ref "IC3") (pin "10") (pinfunction "SCL_10") (pintype "input"))
      (node (ref "IC5") (pin "10") (pinfunction "SCL_10") (pintype "input"))
      (node (ref "STM_CHIP") (pin "11") (pinfunction "PC3_11") (pintype "bidirectional"))
    )
    (net (code "168") (name "SR_SHCP") (class "Default")
      (node (ref "IC2") (pin "11") (pinfunction "SCK_11") (pintype "input"))
      (node (ref "IC3") (pin "11") (pinfunction "SCK_11") (pintype "input"))
      (node (ref "IC5") (pin "11") (pinfunction "SCK_11") (pintype "input"))
      (node (ref "STM_CHIP") (pin "10") (pinfunction "PC2_10") (pintype "bidirectional"))
    )
    (net (code "169") (name "SR_STCP") (class "Default")
      (node (ref "IC2") (pin "12") (pinfunction "RCK_12") (pintype "input"))
      (node (ref "IC3") (pin "12") (pinfunction "RCK_12") (pintype "input"))
      (node (ref "IC5") (pin "12") (pinfunction "RCK_12") (pintype "input"))
      (node (ref "STM_CHIP") (pin "9") (pinfunction "PC1_9") (pintype "bidirectional"))
    )
    (net (code "170") (name "SWD_NRST") (class "Default")
      (node (ref "S1") (pin "1") (pinfunction "1_1") (pintype "passive"))
      (node (ref "S1") (pin "2") (pinfunction "2_2") (pintype "passive"))
      (node (ref "STM-C8") (pin "1") (pinfunction "1_1") (pintype "passive"))
      (node (ref "STM_CHIP") (pin "7") (pinfunction "NRST_7") (pintype "bidirectional"))
    )
    (net (code "171") (name "SWD_TCK") (class "Default")
      (node (ref "STM-SWD") (pin "2") (pinfunction "2_2") (pintype "passive"))
      (node (ref "STM_CHIP") (pin "49") (pinfunction "PA14_49") (pintype "bidirectional"))
    )
    (net (code "172") (name "SWD_TMS") (class "Default")
      (node (ref "STM-SWD") (pin "4") (pinfunction "4_4") (pintype "passive"))
      (node (ref "STM_CHIP") (pin "46") (pinfunction "PA13_46") (pintype "bidirectional"))
    )
    (net (code "173") (name "TXN") (class "Default")
      (node (ref "ETH-R2") (pin "1") (pinfunction "1_1") (pintype "passive"))
      (node (ref "ETHERNET") (pin "2") (pinfunction "TX-_2") (pintype "bidirectional"))
      (node (ref "U2") (pin "1") (pinfunction "TXN_1") (pintype "passive"))
    )
    (net (code "174") (name "TXP") (class "Default")
      (node (ref "ETH-R1") (pin "1") (pinfunction "1_1") (pintype "passive"))
      (node (ref "ETHERNET") (pin "1") (pinfunction "TX+_1") (pintype "bidirectional"))
      (node (ref "U2") (pin "2") (pinfunction "TXP_2") (pintype "passive"))
    )
    (net (code "175") (name "T_CLK") (class "Default")
      (node (ref "STM_CHIP") (pin "27") (pinfunction "PB1_27") (pintype "bidirectional"))
      (node (ref "U$13") (pin "T_CLK") (pinfunction "T_CLK_T_CLK") (pintype "bidirectional"))
    )
    (net (code "176") (name "T_DIN") (class "Default")
      (node (ref "STM_CHIP") (pin "29") (pinfunction "PB10_29") (pintype "bidirectional"))
      (node (ref "U$13") (pin "T_DIN") (pinfunction "T_DIN_T_DIN") (pintype "bidirectional"))
    )
    (net (code "177") (name "T_DO") (class "Default")
      (node (ref "STM_CHIP") (pin "30") (pinfunction "PB11_30") (pintype "bidirectional"))
      (node (ref "U$13") (pin "T_DO") (pinfunction "T_DO_T_DO") (pintype "bidirectional"))
    )
    (net (code "178") (name "T_IRQ") (class "Default")
      (node (ref "STM_CHIP") (pin "28") (pinfunction "PB2_28") (pintype "bidirectional"))
      (node (ref "U$13") (pin "T_IRQ") (pinfunction "T_IRQ_T_IRQ") (pintype "bidirectional"))
    )
    (net (code "179") (name "USB_DM") (class "Default")
      (node (ref "STM_CHIP") (pin "44") (pinfunction "PA11_44") (pintype "bidirectional"))
      (node (ref "USB_IN") (pin "D-1") (pinfunction "D-_D-1") (pintype "bidirectional"))
    )
    (net (code "180") (name "USB_DP") (class "Default")
      (node (ref "STM_CHIP") (pin "45") (pinfunction "PA12_45") (pintype "bidirectional"))
      (node (ref "USB_IN") (pin "D+1") (pinfunction "D+_D+1") (pintype "bidirectional"))
    )
    (net (code "181") (name "USIM_CLK") (class "Default")
      (node (ref "SIM900-R2") (pin "2") (pinfunction "2_2") (pintype "passive"))
      (node (ref "U$8") (pin "SIM_CLK") (pinfunction "SIM_CLK_SIM_CLK") (pintype "bidirectional"))
    )
    (net (code "182") (name "USIM_DATA") (class "Default")
      (node (ref "SIM900-R3") (pin "2") (pinfunction "2_2") (pintype "passive"))
      (node (ref "U$8") (pin "SIM_IO") (pinfunction "SIM_IO_SIM_IO") (pintype "bidirectional"))
    )
    (net (code "183") (name "USIM_RESET") (class "Default")
      (node (ref "SIM900-R1") (pin "2") (pinfunction "2_2") (pintype "passive"))
      (node (ref "U$8") (pin "SIM_RST") (pinfunction "SIM_RST_SIM_RST") (pintype "bidirectional"))
    )
    (net (code "184") (name "USIM_VCC") (class "Default")
      (node (ref "IC1") (pin "P$30") (pinfunction "SIM_VDD_P$30") (pintype "power_in"))
      (node (ref "SIM900-C4") (pin "1") (pinfunction "1_1") (pintype "passive"))
      (node (ref "SIM900-C5") (pin "1") (pinfunction "1_1") (pintype "passive"))
      (node (ref "SIM_C1") (pin "2") (pinfunction "2_2") (pintype "passive"))
      (node (ref "SIM_C2") (pin "2") (pinfunction "2_2") (pintype "passive"))
      (node (ref "U$8") (pin "SIM_VDD") (pinfunction "SIM_VDD_SIM_VDD") (pintype "bidirectional"))
    )
    (net (code "185") (name "VBAT") (class "Default")
      (node (ref "BAT1") (pin "PWR@1") (pinfunction "+_PWR@1") (pintype "power_in"))
      (node (ref "STM_CHIP") (pin "1") (pinfunction "VLCD_1") (pintype "power_in"))
    )
    (net (code "186") (name "VCC") (class "Default")
      (node (ref "ETH-R1") (pin "2") (pinfunction "2_2") (pintype "passive"))
      (node (ref "ETH-R2") (pin "2") (pinfunction "2_2") (pintype "passive"))
      (node (ref "ETH-R3") (pin "2") (pinfunction "2_2") (pintype "passive"))
      (node (ref "STM-C9") (pin "1") (pinfunction "1_1") (pintype "passive"))
      (node (ref "STM-L1") (pin "2") (pinfunction "2_2") (pintype "passive"))
      (node (ref "STM_CHIP") (pin "13") (pinfunction "VDDA_13") (pintype "power_in"))
      (node (ref "SYS-C4") (pin "1") (pinfunction "1_1") (pintype "passive"))
      (node (ref "SYS-R2") (pin "2") (pinfunction "2_2") (pintype "passive"))
      (node (ref "U2") (pin "11") (pinfunction "AVDD_11") (pintype "passive"))
      (node (ref "U2") (pin "15") (pinfunction "AVDD_15") (pintype "passive"))
      (node (ref "U2") (pin "17") (pinfunction "AVDD_17") (pintype "passive"))
      (node (ref "U2") (pin "21") (pinfunction "AVDD_21") (pintype "passive"))
      (node (ref "U2") (pin "4") (pinfunction "AVDD_4") (pintype "passive"))
      (node (ref "U2") (pin "8") (pinfunction "AVDD_8") (pintype "passive"))
      (node (ref "W5500-C10") (pin "1") (pinfunction "1_1") (pintype "passive"))
      (node (ref "W5500-C11") (pin "1") (pinfunction "1_1") (pintype "passive"))
      (node (ref "W5500-C12") (pin "+") (pinfunction "+_+") (pintype "passive"))
      (node (ref "W5500-C6") (pin "1") (pinfunction "1_1") (pintype "passive"))
      (node (ref "W5500-C7") (pin "1") (pinfunction "1_1") (pintype "passive"))
      (node (ref "W5500-C8") (pin "1") (pinfunction "1_1") (pintype "passive"))
      (node (ref "W5500-C9") (pin "1") (pinfunction "1_1") (pintype "passive"))
    )
    (net (code "187") (name "VDD") (class "Default")
      (node (ref "CC_C14") (pin "1") (pinfunction "1_1") (pintype "passive"))
      (node (ref "CC_C20") (pin "1") (pinfunction "1_1") (pintype "passive"))
      (node (ref "CC_C8") (pin "1") (pinfunction "1_1") (pintype "passive"))
      (node (ref "DHT-R1") (pin "1") (pinfunction "1_1") (pintype "passive"))
      (node (ref "ESP_EXT") (pin "1") (pinfunction "1_1") (pintype "passive"))
      (node (ref "ETHERNET") (pin "12") (pinfunction "LED2_A_12") (pintype "bidirectional"))
      (node (ref "ETHERNET") (pin "9") (pinfunction "LED1_A_9") (pintype "bidirectional"))
      (node (ref "IC2") (pin "16") (pinfunction "VCC_16") (pintype "power_in"))
      (node (ref "IC3") (pin "16") (pinfunction "VCC_16") (pintype "power_in"))
      (node (ref "IC5") (pin "16") (pinfunction "VCC_16") (pintype "power_in"))
      (node (ref "LCD-R1") (pin "2") (pinfunction "2_2") (pintype "passive"))
      (node (ref "PWR-SWT") (pin "1") (pinfunction "1_1") (pintype "passive"))
      (node (ref "RW5500-1") (pin "2") (pinfunction "1_2") (pintype "passive"))
      (node (ref "RW5500-1") (pin "3") (pinfunction "1_3") (pintype "passive"))
      (node (ref "RW5500-1") (pin "4") (pinfunction "1_4") (pintype "passive"))
      (node (ref "RW5500-3") (pin "1") (pinfunction "1_1") (pintype "passive"))
      (node (ref "R_VREG") (pin "2") (pinfunction "2_2") (pintype "passive"))
      (node (ref "SENSOR-DHT") (pin "1") (pinfunction "1_1") (pintype "passive"))
      (node (ref "SIM900-R4") (pin "2") (pinfunction "2_2") (pintype "passive"))
      (node (ref "SIM900-R7") (pin "2") (pinfunction "2_2") (pintype "passive"))
      (node (ref "STM-C1") (pin "2") (pinfunction "2_2") (pintype "passive"))
      (node (ref "STM-C10") (pin "1") (pinfunction "1_1") (pintype "passive"))
      (node (ref "STM-C11") (pin "1") (pinfunction "1_1") (pintype "passive"))
      (node (ref "STM-C12") (pin "1") (pinfunction "1_1") (pintype "passive"))
      (node (ref "STM-C13") (pin "1") (pinfunction "1_1") (pintype "passive"))
      (node (ref "STM-L1") (pin "1") (pinfunction "1_1") (pintype "passive"))
      (node (ref "STM-SWD") (pin "1") (pinfunction "1_1") (pintype "passive"))
      (node (ref "STM-USART") (pin "1") (pinfunction "1_1") (pintype "passive"))
      (node (ref "STM_CHIP") (pin "19") (pinfunction "VDD_4_19") (pintype "power_in"))
      (node (ref "STM_CHIP") (pin "32") (pinfunction "VDD_1_32") (pintype "power_in"))
      (node (ref "STM_CHIP") (pin "48") (pinfunction "VDD_2_48") (pintype "power_in"))
      (node (ref "STM_CHIP") (pin "64") (pinfunction "VDD_3_64") (pintype "power_in"))
      (node (ref "SYS-C3") (pin "1") (pinfunction "1_1") (pintype "passive"))
      (node (ref "SYS-L2") (pin "2") (pinfunction "2_2") (pintype "passive"))
      (node (ref "SYS-R2") (pin "1") (pinfunction "1_1") (pintype "passive"))
      (node (ref "U$13") (pin "LCD_VCC") (pinfunction "LCD_VCC_LCD_VCC") (pintype "power_in"))
      (node (ref "U$4") (pin "11") (pinfunction "AVDD_11") (pintype "power_in"))
      (node (ref "U$4") (pin "14") (pinfunction "AVDD_14") (pintype "power_in"))
      (node (ref "U$4") (pin "16") (pinfunction "AVDD_16") (pintype "power_in"))
      (node (ref "U$4") (pin "20") (pinfunction "AVDD_20") (pintype "power_in"))
      (node (ref "U$4") (pin "22") (pinfunction "AVDD_22") (pintype "power_in"))
      (node (ref "U$4") (pin "24") (pinfunction "AVDD-GUARD_24") (pintype "power_in"))
      (node (ref "U$4") (pin "8") (pinfunction "DVDD_8") (pintype "power_in"))
      (node (ref "U2") (pin "28") (pinfunction "VDD_28") (pintype "passive"))
      (node (ref "W5500-C13") (pin "+") (pinfunction "+_+") (pintype "passive"))
      (node (ref "W5500-C5") (pin "1") (pinfunction "1_1") (pintype "passive"))
      (node (ref "W5500-R13") (pin "2") (pinfunction "2_2") (pintype "passive"))
    )
    (net (code "188") (name "VESP") (class "Default")
      (node (ref "ESP-C1") (pin "1") (pinfunction "1_1") (pintype "passive"))
      (node (ref "ESP-GPIO0") (pin "1") (pinfunction "1_1") (pintype "passive"))
      (node (ref "ESP_EXT") (pin "2") (pinfunction "2_2") (pintype "passive"))
      (node (ref "U$5") (pin "CH_PD") (pinfunction "CH_PD_CH_PD") (pintype "bidirectional"))
      (node (ref "U$5") (pin "GPIO02") (pinfunction "GPIO2_GPIO02") (pintype "bidirectional"))
      (node (ref "U$5") (pin "REST") (pinfunction "REST_REST") (pintype "bidirectional"))
      (node (ref "U$5") (pin "VCC") (pinfunction "VCC_VCC") (pintype "power_in"))
    )
    (net (code "189") (name "unconnected-(IC1-ADC-PadP$25)") (class "Default")
      (node (ref "IC1") (pin "P$25") (pinfunction "ADC_P$25") (pintype "bidirectional"))
    )
    (net (code "190") (name "unconnected-(IC1-CTS-PadP$7)") (class "Default")
      (node (ref "IC1") (pin "P$7") (pinfunction "CTS_P$7") (pintype "output"))
    )
    (net (code "191") (name "unconnected-(IC1-DBG_RXD-PadP$28)") (class "Default")
      (node (ref "IC1") (pin "P$28") (pinfunction "DBG_RXD_P$28") (pintype "input"))
    )
    (net (code "192") (name "unconnected-(IC1-DBG_TXD-PadP$27)") (class "Default")
      (node (ref "IC1") (pin "P$27") (pinfunction "DBG_TXD_P$27") (pintype "output"))
    )
    (net (code "193") (name "unconnected-(IC1-DCD-PadP$5)") (class "Default")
      (node (ref "IC1") (pin "P$5") (pinfunction "DCD_P$5") (pintype "output"))
    )
    (net (code "194") (name "unconnected-(IC1-DISP_CLK-PadP$11)") (class "Default")
      (node (ref "IC1") (pin "P$11") (pinfunction "DISP_CLK_P$11") (pintype "bidirectional"))
    )
    (net (code "195") (name "unconnected-(IC1-DISP_CS-PadP$14)") (class "Default")
      (node (ref "IC1") (pin "P$14") (pinfunction "DISP_CS_P$14") (pintype "bidirectional"))
    )
    (net (code "196") (name "unconnected-(IC1-DISP_DATA-PadP$12)") (class "Default")
      (node (ref "IC1") (pin "P$12") (pinfunction "DISP_DATA_P$12") (pintype "bidirectional"))
    )
    (net (code "197") (name "unconnected-(IC1-DISP_DC-PadP$13)") (class "Default")
      (node (ref "IC1") (pin "P$13") (pinfunction "DISP_DC_P$13") (pintype "bidirectional"))
    )
    (net (code "198") (name "unconnected-(IC1-DTR-PadP$3)") (class "Default")
      (node (ref "IC1") (pin "P$3") (pinfunction "DTR_P$3") (pintype "input"))
    )
    (net (code "199") (name "unconnected-(IC1-GPIO1{slash}KBR4-PadP$40)") (class "Default")
      (node (ref "IC1") (pin "P$40") (pinfunction "GPIO1/KBR4_P$40") (pintype "bidirectional"))
    )
    (net (code "200") (name "unconnected-(IC1-GPIO2{slash}KBR3-PadP$41)") (class "Default")
      (node (ref "IC1") (pin "P$41") (pinfunction "GPIO2/KBR3_P$41") (pintype "bidirectional"))
    )
    (net (code "201") (name "unconnected-(IC1-GPIO3{slash}KBR2-PadP$42)") (class "Default")
      (node (ref "IC1") (pin "P$42") (pinfunction "GPIO3/KBR2_P$42") (pintype "bidirectional"))
    )
    (net (code "202") (name "unconnected-(IC1-GPIO4{slash}KBR1-PadP$43)") (class "Default")
      (node (ref "IC1") (pin "P$43") (pinfunction "GPIO4/KBR1_P$43") (pintype "bidirectional"))
    )
    (net (code "203") (name "unconnected-(IC1-GPIO5{slash}KBR0-PadP$44)") (class "Default")
      (node (ref "IC1") (pin "P$44") (pinfunction "GPIO5/KBR0_P$44") (pintype "bidirectional"))
    )
    (net (code "204") (name "unconnected-(IC1-GPIO6{slash}KBC4-PadP$47)") (class "Default")
      (node (ref "IC1") (pin "P$47") (pinfunction "GPIO6/KBC4_P$47") (pintype "bidirectional"))
    )
    (net (code "205") (name "unconnected-(IC1-GPIO7{slash}KBC3-PadP$48)") (class "Default")
      (node (ref "IC1") (pin "P$48") (pinfunction "GPIO7/KBC3_P$48") (pintype "bidirectional"))
    )
    (net (code "206") (name "unconnected-(IC1-GPIO8{slash}KBC2-PadP$49)") (class "Default")
      (node (ref "IC1") (pin "P$49") (pinfunction "GPIO8/KBC2_P$49") (pintype "bidirectional"))
    )
    (net (code "207") (name "unconnected-(IC1-GPIO9{slash}KBC1-PadP$50)") (class "Default")
      (node (ref "IC1") (pin "P$50") (pinfunction "GPIO9/KBC1_P$50") (pintype "bidirectional"))
    )
    (net (code "208") (name "unconnected-(IC1-GPIO10-PadP$51)") (class "Default")
      (node (ref "IC1") (pin "P$51") (pinfunction "GPIO10_P$51") (pintype "bidirectional"))
    )
    (net (code "209") (name "unconnected-(IC1-LINEIN_L-PadP$24)") (class "Default")
      (node (ref "IC1") (pin "P$24") (pinfunction "LINEIN_L_P$24") (pintype "bidirectional"))
    )
    (net (code "210") (name "unconnected-(IC1-LINEIN_R-PadP$23)") (class "Default")
      (node (ref "IC1") (pin "P$23") (pinfunction "LINEIN_R_P$23") (pintype "bidirectional"))
    )
    (net (code "211") (name "unconnected-(IC1-MIC_N-PadP$20)") (class "Default")
      (node (ref "IC1") (pin "P$20") (pinfunction "MIC_N_P$20") (pintype "bidirectional"))
    )
    (net (code "212") (name "unconnected-(IC1-MIC_P-PadP$19)") (class "Default")
      (node (ref "IC1") (pin "P$19") (pinfunction "MIC_P_P$19") (pintype "bidirectional"))
    )
    (net (code "213") (name "unconnected-(IC1-NC-PadP$2)") (class "Default")
      (node (ref "IC1") (pin "P$2") (pinfunction "NC_P$2") (pintype "no_connect"))
    )
    (net (code "214") (name "unconnected-(IC1-NC-PadP$6)") (class "Default")
      (node (ref "IC1") (pin "P$6") (pinfunction "NC_P$6") (pintype "no_connect"))
    )
    (net (code "215") (name "unconnected-(IC1-PWM1-PadP$35)") (class "Default")
      (node (ref "IC1") (pin "P$35") (pinfunction "PWM1_P$35") (pintype "bidirectional"))
    )
    (net (code "216") (name "unconnected-(IC1-PWM2-PadP$36)") (class "Default")
      (node (ref "IC1") (pin "P$36") (pinfunction "PWM2_P$36") (pintype "bidirectional"))
    )
    (net (code "217") (name "unconnected-(IC1-RI-PadP$4)") (class "Default")
      (node (ref "IC1") (pin "P$4") (pinfunction "RI_P$4") (pintype "output"))
    )
    (net (code "218") (name "unconnected-(IC1-RTS-PadP$8)") (class "Default")
      (node (ref "IC1") (pin "P$8") (pinfunction "RTS_P$8") (pintype "input"))
    )
    (net (code "219") (name "unconnected-(IC1-SCL-PadP$38)") (class "Default")
      (node (ref "IC1") (pin "P$38") (pinfunction "SCL_P$38") (pintype "bidirectional"))
    )
    (net (code "220") (name "unconnected-(IC1-SDA-PadP$37)") (class "Default")
      (node (ref "IC1") (pin "P$37") (pinfunction "SDA_P$37") (pintype "bidirectional"))
    )
    (net (code "221") (name "unconnected-(IC1-SIM_PRESENCE-PadP$34)") (class "Default")
      (node (ref "IC1") (pin "P$34") (pinfunction "SIM_PRESENCE_P$34") (pintype "bidirectional"))
    )
    (net (code "222") (name "unconnected-(IC1-SPK_N-PadP$22)") (class "Default")
      (node (ref "IC1") (pin "P$22") (pinfunction "SPK_N_P$22") (pintype "bidirectional"))
    )
    (net (code "223") (name "unconnected-(IC1-SPK_P-PadP$21)") (class "Default")
      (node (ref "IC1") (pin "P$21") (pinfunction "SPK_P_P$21") (pintype "bidirectional"))
    )
    (net (code "224") (name "unconnected-(IC1-VDD_EXT-PadP$15)") (class "Default")
      (node (ref "IC1") (pin "P$15") (pinfunction "VDD_EXT_P$15") (pintype "bidirectional"))
    )
    (net (code "225") (name "unconnected-(IC5A-QE-Pad4)") (class "Default")
      (node (ref "IC5") (pin "4") (pinfunction "QE_4") (pintype "tri_state"))
    )
    (net (code "226") (name "unconnected-(IC5A-QF-Pad5)") (class "Default")
      (node (ref "IC5") (pin "5") (pinfunction "QF_5") (pintype "tri_state"))
    )
    (net (code "227") (name "unconnected-(IC5A-QG-Pad6)") (class "Default")
      (node (ref "IC5") (pin "6") (pinfunction "QG_6") (pintype "tri_state"))
    )
    (net (code "228") (name "unconnected-(IC5A-QH*-Pad9)") (class "Default")
      (node (ref "IC5") (pin "9") (pinfunction "QH*_9") (pintype "tri_state"))
    )
    (net (code "229") (name "unconnected-(IC5A-QH-Pad7)") (class "Default")
      (node (ref "IC5") (pin "7") (pinfunction "QH_7") (pintype "tri_state"))
    )
    (net (code "230") (name "unconnected-(SENSOR-DHT-Pad3)") (class "Default")
      (node (ref "SENSOR-DHT") (pin "3") (pinfunction "3_3") (pintype "passive"))
    )
    (net (code "231") (name "unconnected-(STM_CHIP-BOOT0-Pad60)") (class "Default")
      (node (ref "STM_CHIP") (pin "60") (pinfunction "BOOT0_60") (pintype "input"))
    )
    (net (code "232") (name "unconnected-(STM_CHIP-PH0_-OSC_IN-Pad5)") (class "Default")
      (node (ref "STM_CHIP") (pin "5") (pinfunction "PH0_-OSC_IN_5") (pintype "bidirectional"))
    )
    (net (code "233") (name "unconnected-(U$5-GPIO4-PadGPIO04)") (class "Default")
      (node (ref "U$5") (pin "GPIO04") (pinfunction "GPIO4_GPIO04") (pintype "bidirectional"))
    )
    (net (code "234") (name "unconnected-(U$5-GPIO5-PadGPIO05)") (class "Default")
      (node (ref "U$5") (pin "GPIO05") (pinfunction "GPIO5_GPIO05") (pintype "bidirectional"))
    )
    (net (code "235") (name "unconnected-(U$5-PadADC)") (class "Default")
      (node (ref "U$5") (pin "ADC") (pinfunction "ADC_ADC") (pintype "bidirectional"))
    )
    (net (code "236") (name "unconnected-(U$5-PadGPIO12)") (class "Default")
      (node (ref "U$5") (pin "GPIO12") (pinfunction "GPIO12_GPIO12") (pintype "bidirectional"))
    )
    (net (code "237") (name "unconnected-(U$5-PadGPIO13)") (class "Default")
      (node (ref "U$5") (pin "GPIO13") (pinfunction "GPIO13_GPIO13") (pintype "bidirectional"))
    )
    (net (code "238") (name "unconnected-(U$5-PadGPIO14)") (class "Default")
      (node (ref "U$5") (pin "GPIO14") (pinfunction "GPIO14_GPIO14") (pintype "bidirectional"))
    )
    (net (code "239") (name "unconnected-(U$5-PadGPIO16)") (class "Default")
      (node (ref "U$5") (pin "GPIO16") (pinfunction "GPIO16_GPIO16") (pintype "bidirectional"))
    )
    (net (code "240") (name "unconnected-(U$8-PadVPP)") (class "Default")
      (node (ref "U$8") (pin "VPP") (pinfunction "VPP_VPP") (pintype "bidirectional"))
    )
    (net (code "241") (name "unconnected-(U2-DNC-Pad7)") (class "Default")
      (node (ref "U2") (pin "7") (pinfunction "DNC_7") (pintype "passive"))
    )
    (net (code "242") (name "unconnected-(U2-DUPLED-Pad26)") (class "Default")
      (node (ref "U2") (pin "26") (pinfunction "DUPLED_26") (pintype "passive"))
    )
    (net (code "243") (name "unconnected-(U2-INT_N-Pad36)") (class "Default")
      (node (ref "U2") (pin "36") (pinfunction "INT_N_36") (pintype "passive"))
    )
    (net (code "244") (name "unconnected-(U2-NC-Pad12)") (class "Default")
      (node (ref "U2") (pin "12") (pinfunction "NC_12") (pintype "passive"))
    )
    (net (code "245") (name "unconnected-(U2-NC-Pad13)") (class "Default")
      (node (ref "U2") (pin "13") (pinfunction "NC_13") (pintype "passive"))
    )
    (net (code "246") (name "unconnected-(U2-NC-Pad46)") (class "Default")
      (node (ref "U2") (pin "46") (pinfunction "NC_46") (pintype "passive"))
    )
    (net (code "247") (name "unconnected-(U2-NC-Pad47)") (class "Default")
      (node (ref "U2") (pin "47") (pinfunction "NC_47") (pintype "passive"))
    )
    (net (code "248") (name "unconnected-(U2-SPDLED-Pad24)") (class "Default")
      (node (ref "U2") (pin "24") (pinfunction "SPDLED_24") (pintype "passive"))
    )
    (net (code "249") (name "unconnected-(U2-VBG-Pad18)") (class "Default")
      (node (ref "U2") (pin "18") (pinfunction "VBG_18") (pintype "passive"))
    )
    (net (code "250") (name "unconnected-(USB_IN-ID-PadID1)") (class "Default")
      (node (ref "USB_IN") (pin "ID1") (pinfunction "ID_ID1") (pintype "bidirectional"))
    )
  )
)
